# OpenDeck-r1_2_2.net
KiCad netlist of a schematic drawn in EAGLE
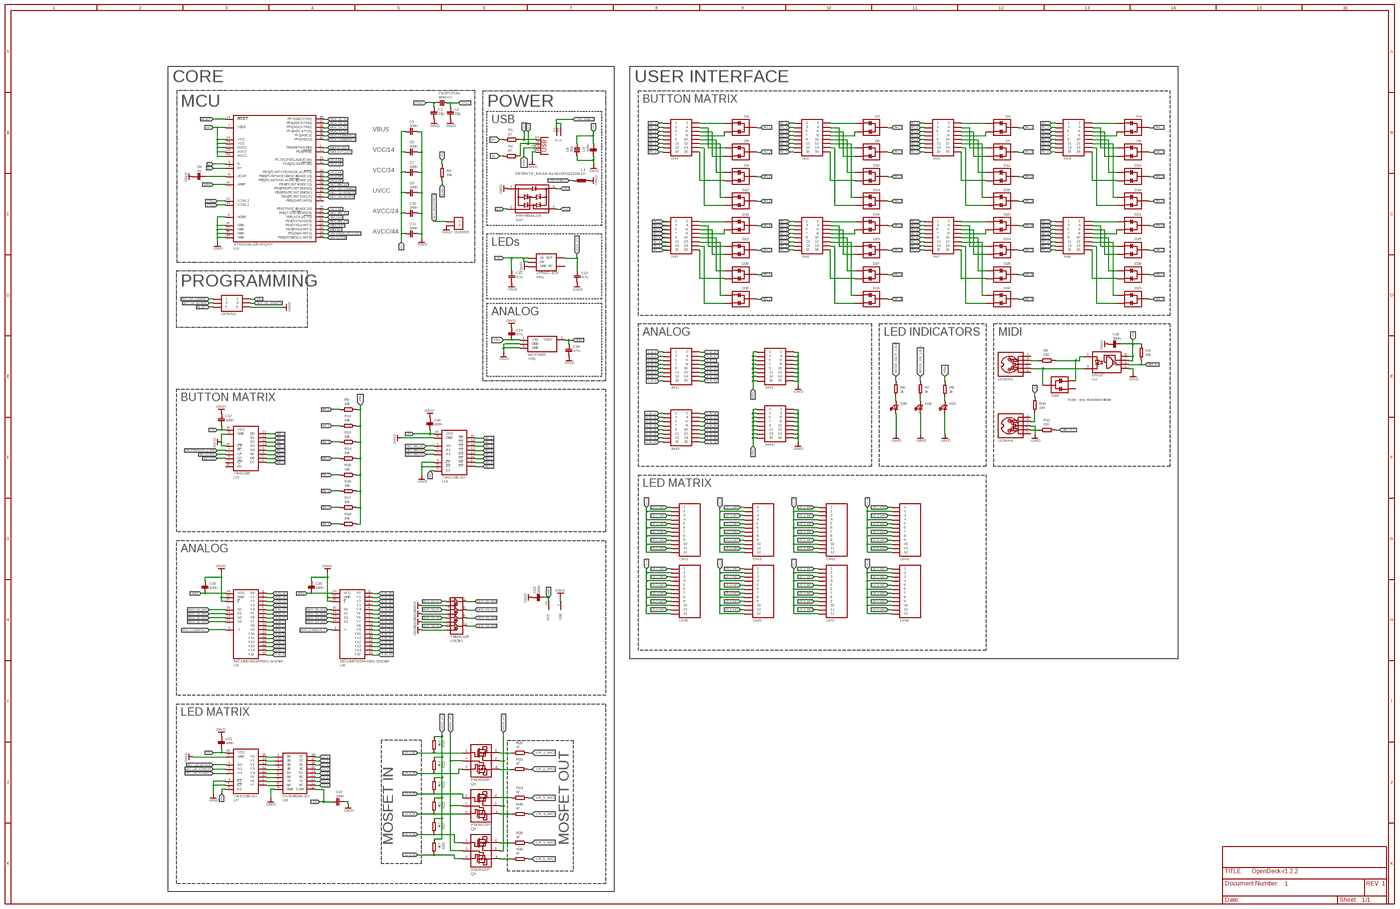
[diagram p0: schematic, sheet 1, overview]
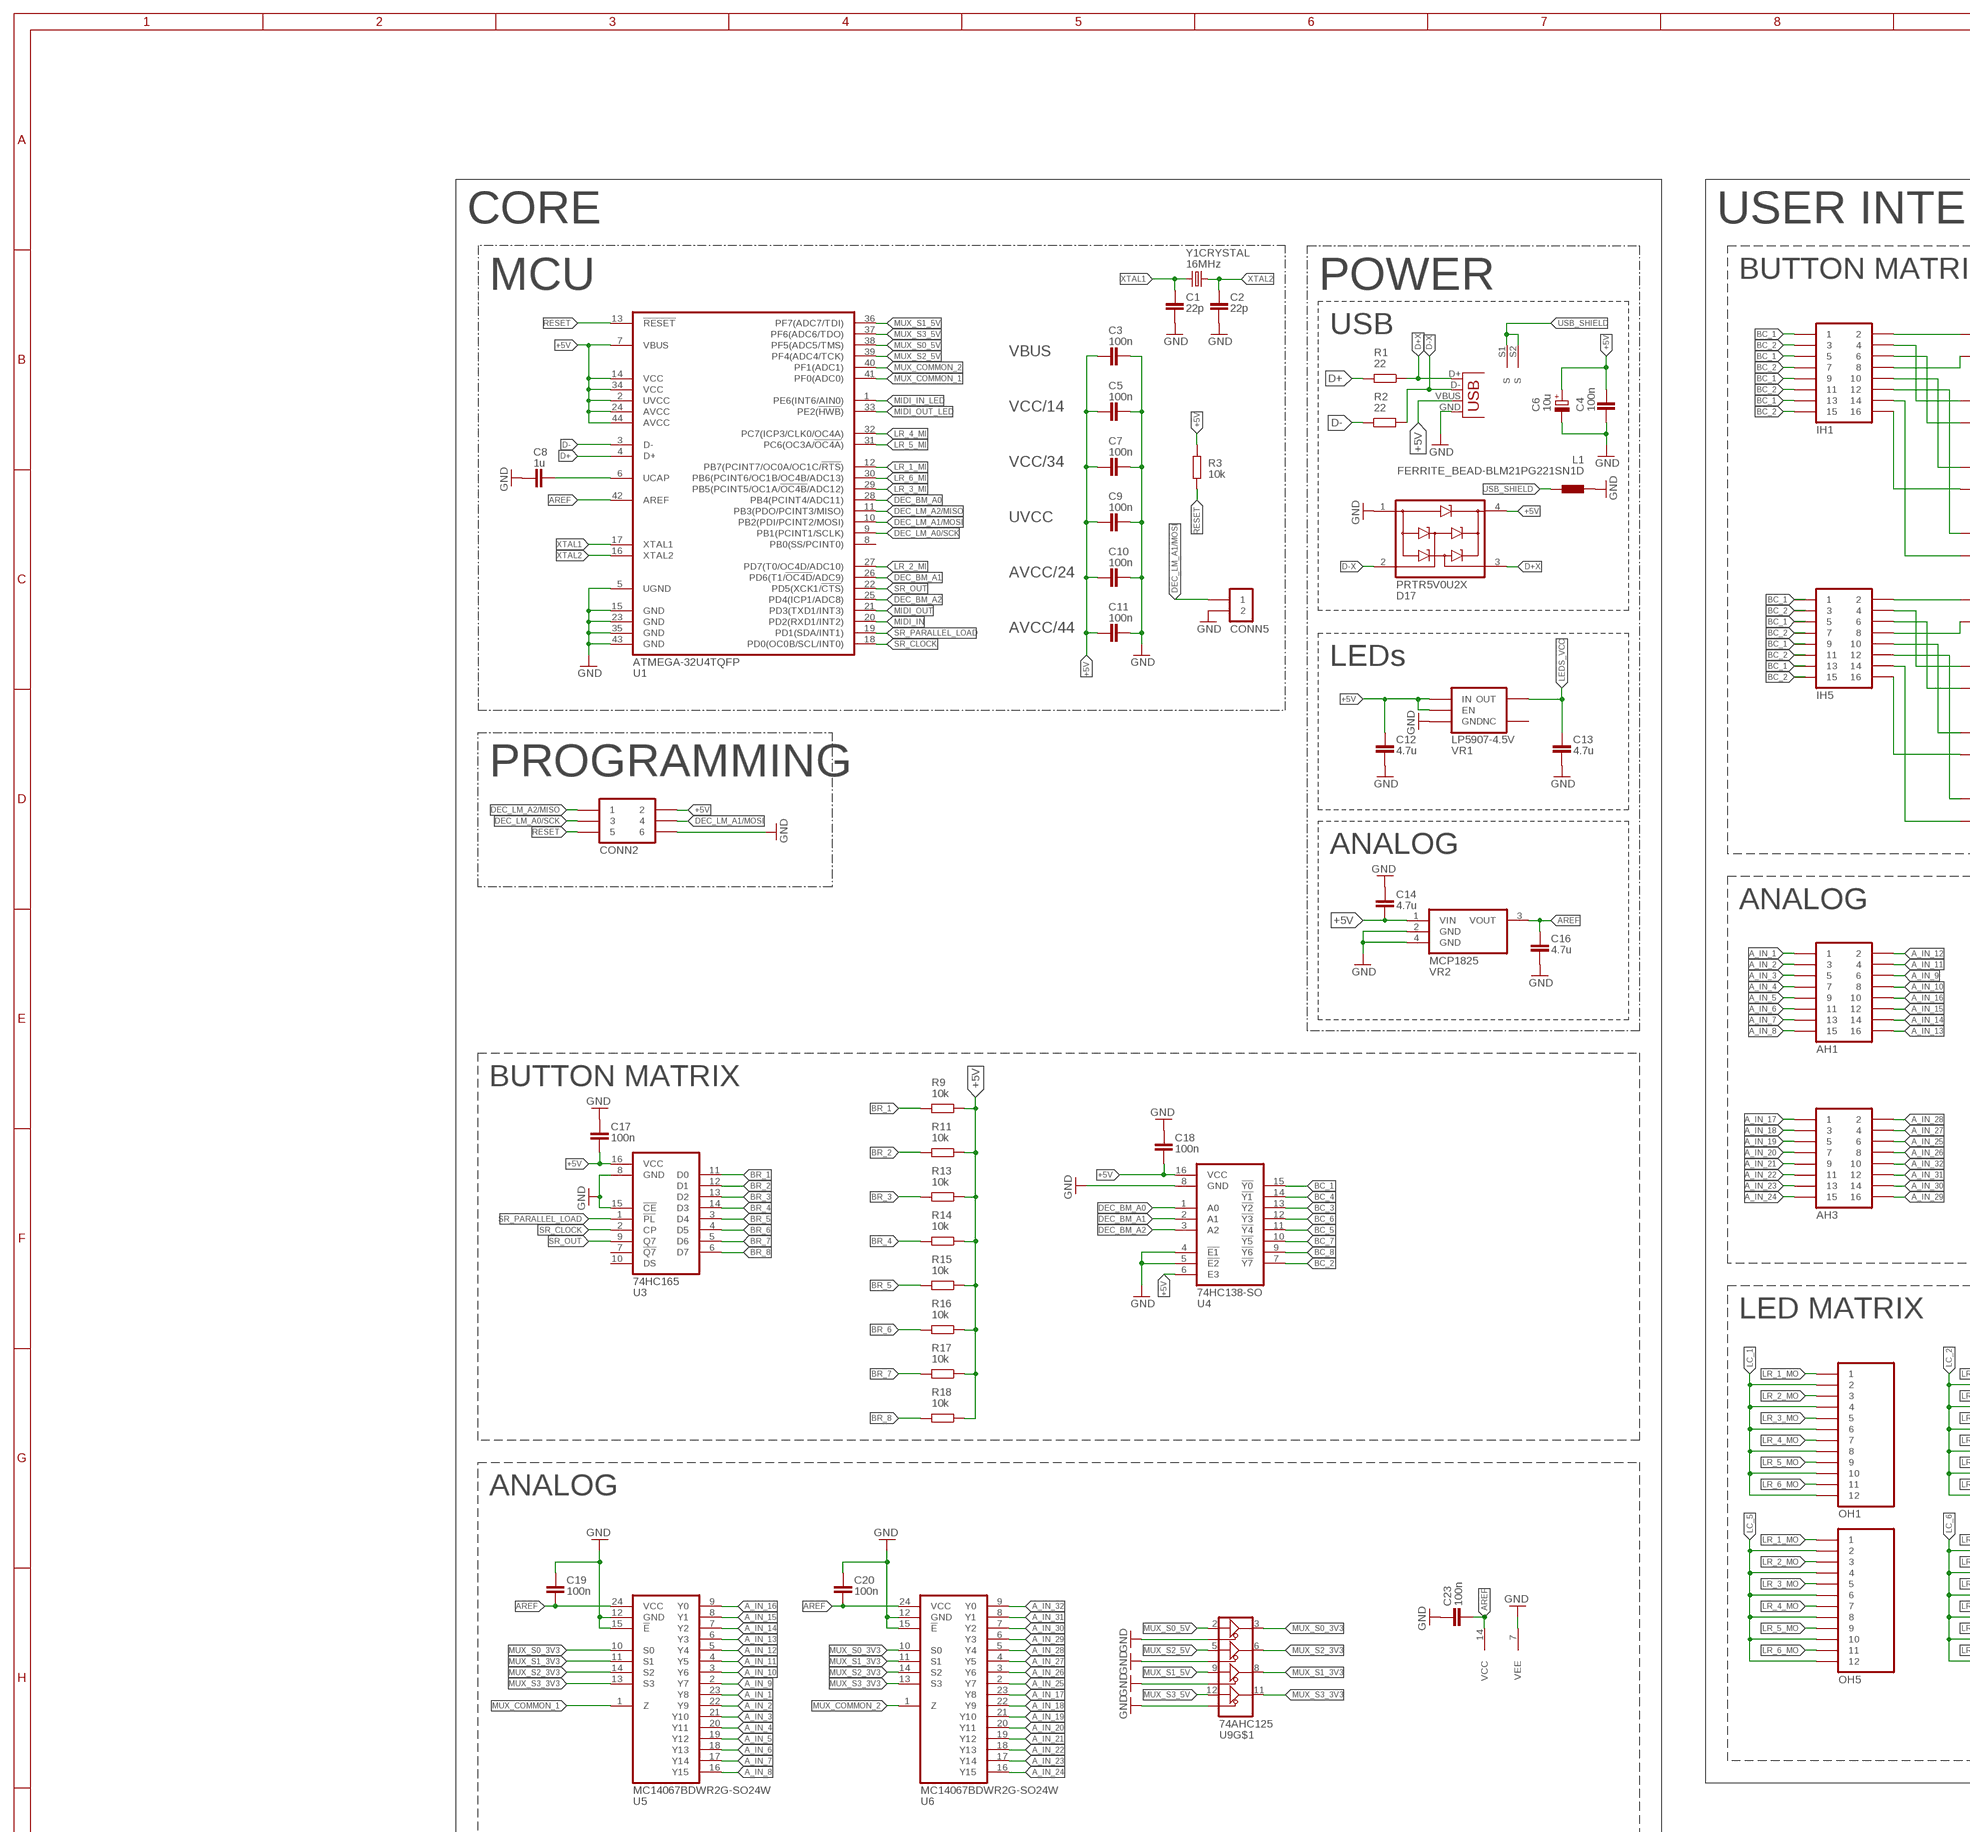
[diagram p1: schematic, sheet 1, part 1 of 4]
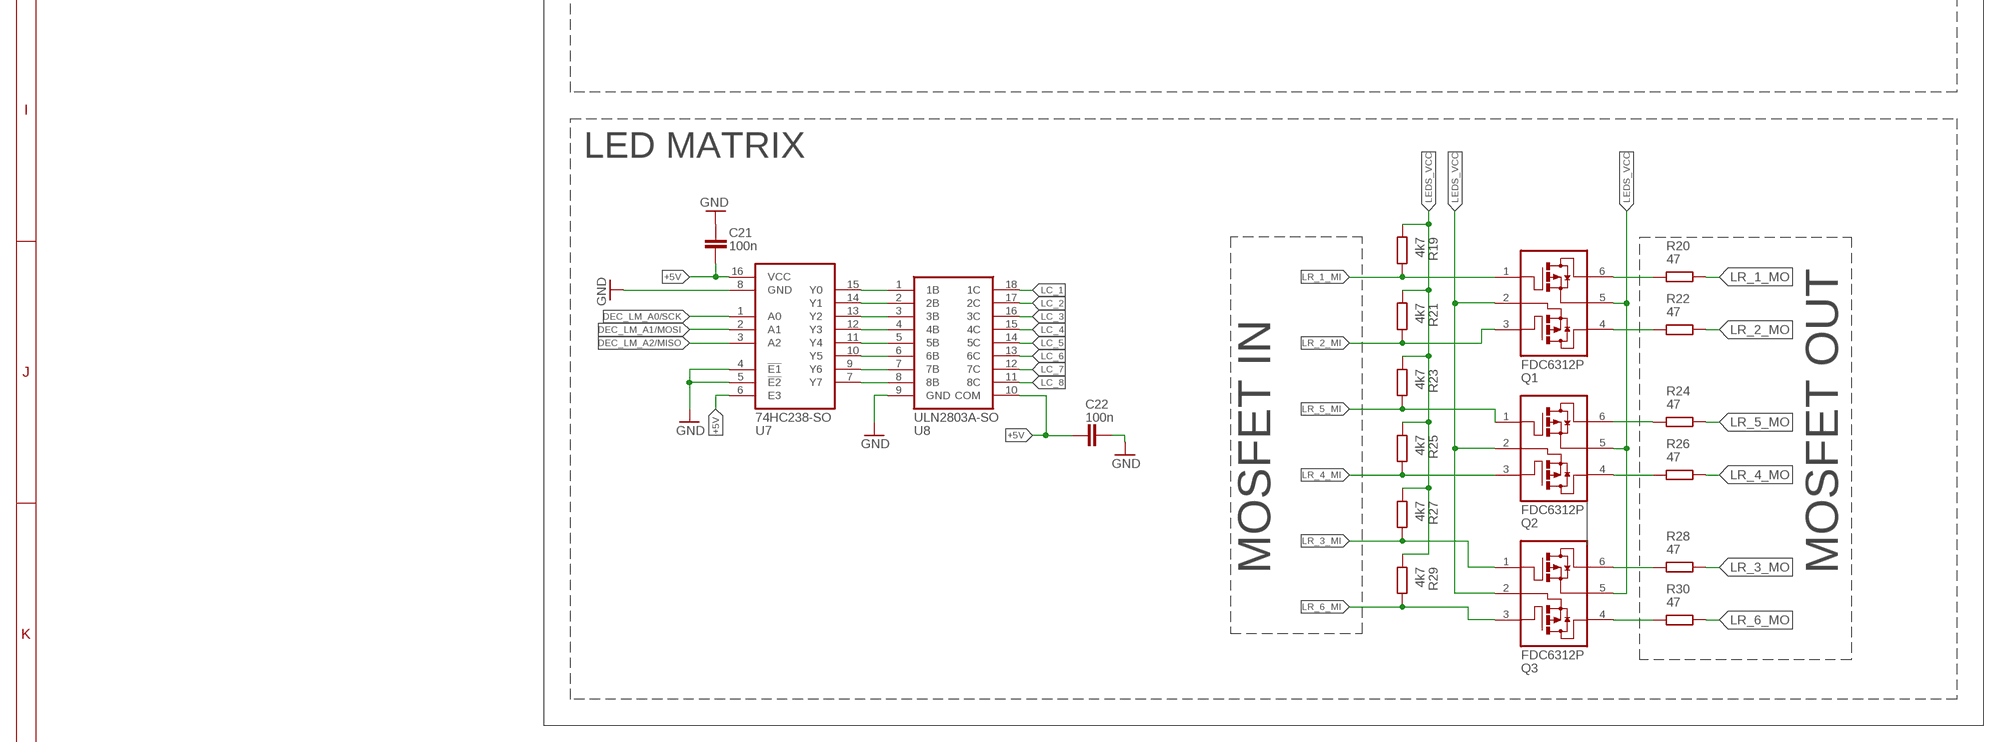
[diagram p2: schematic, sheet 1, part 2 of 4]
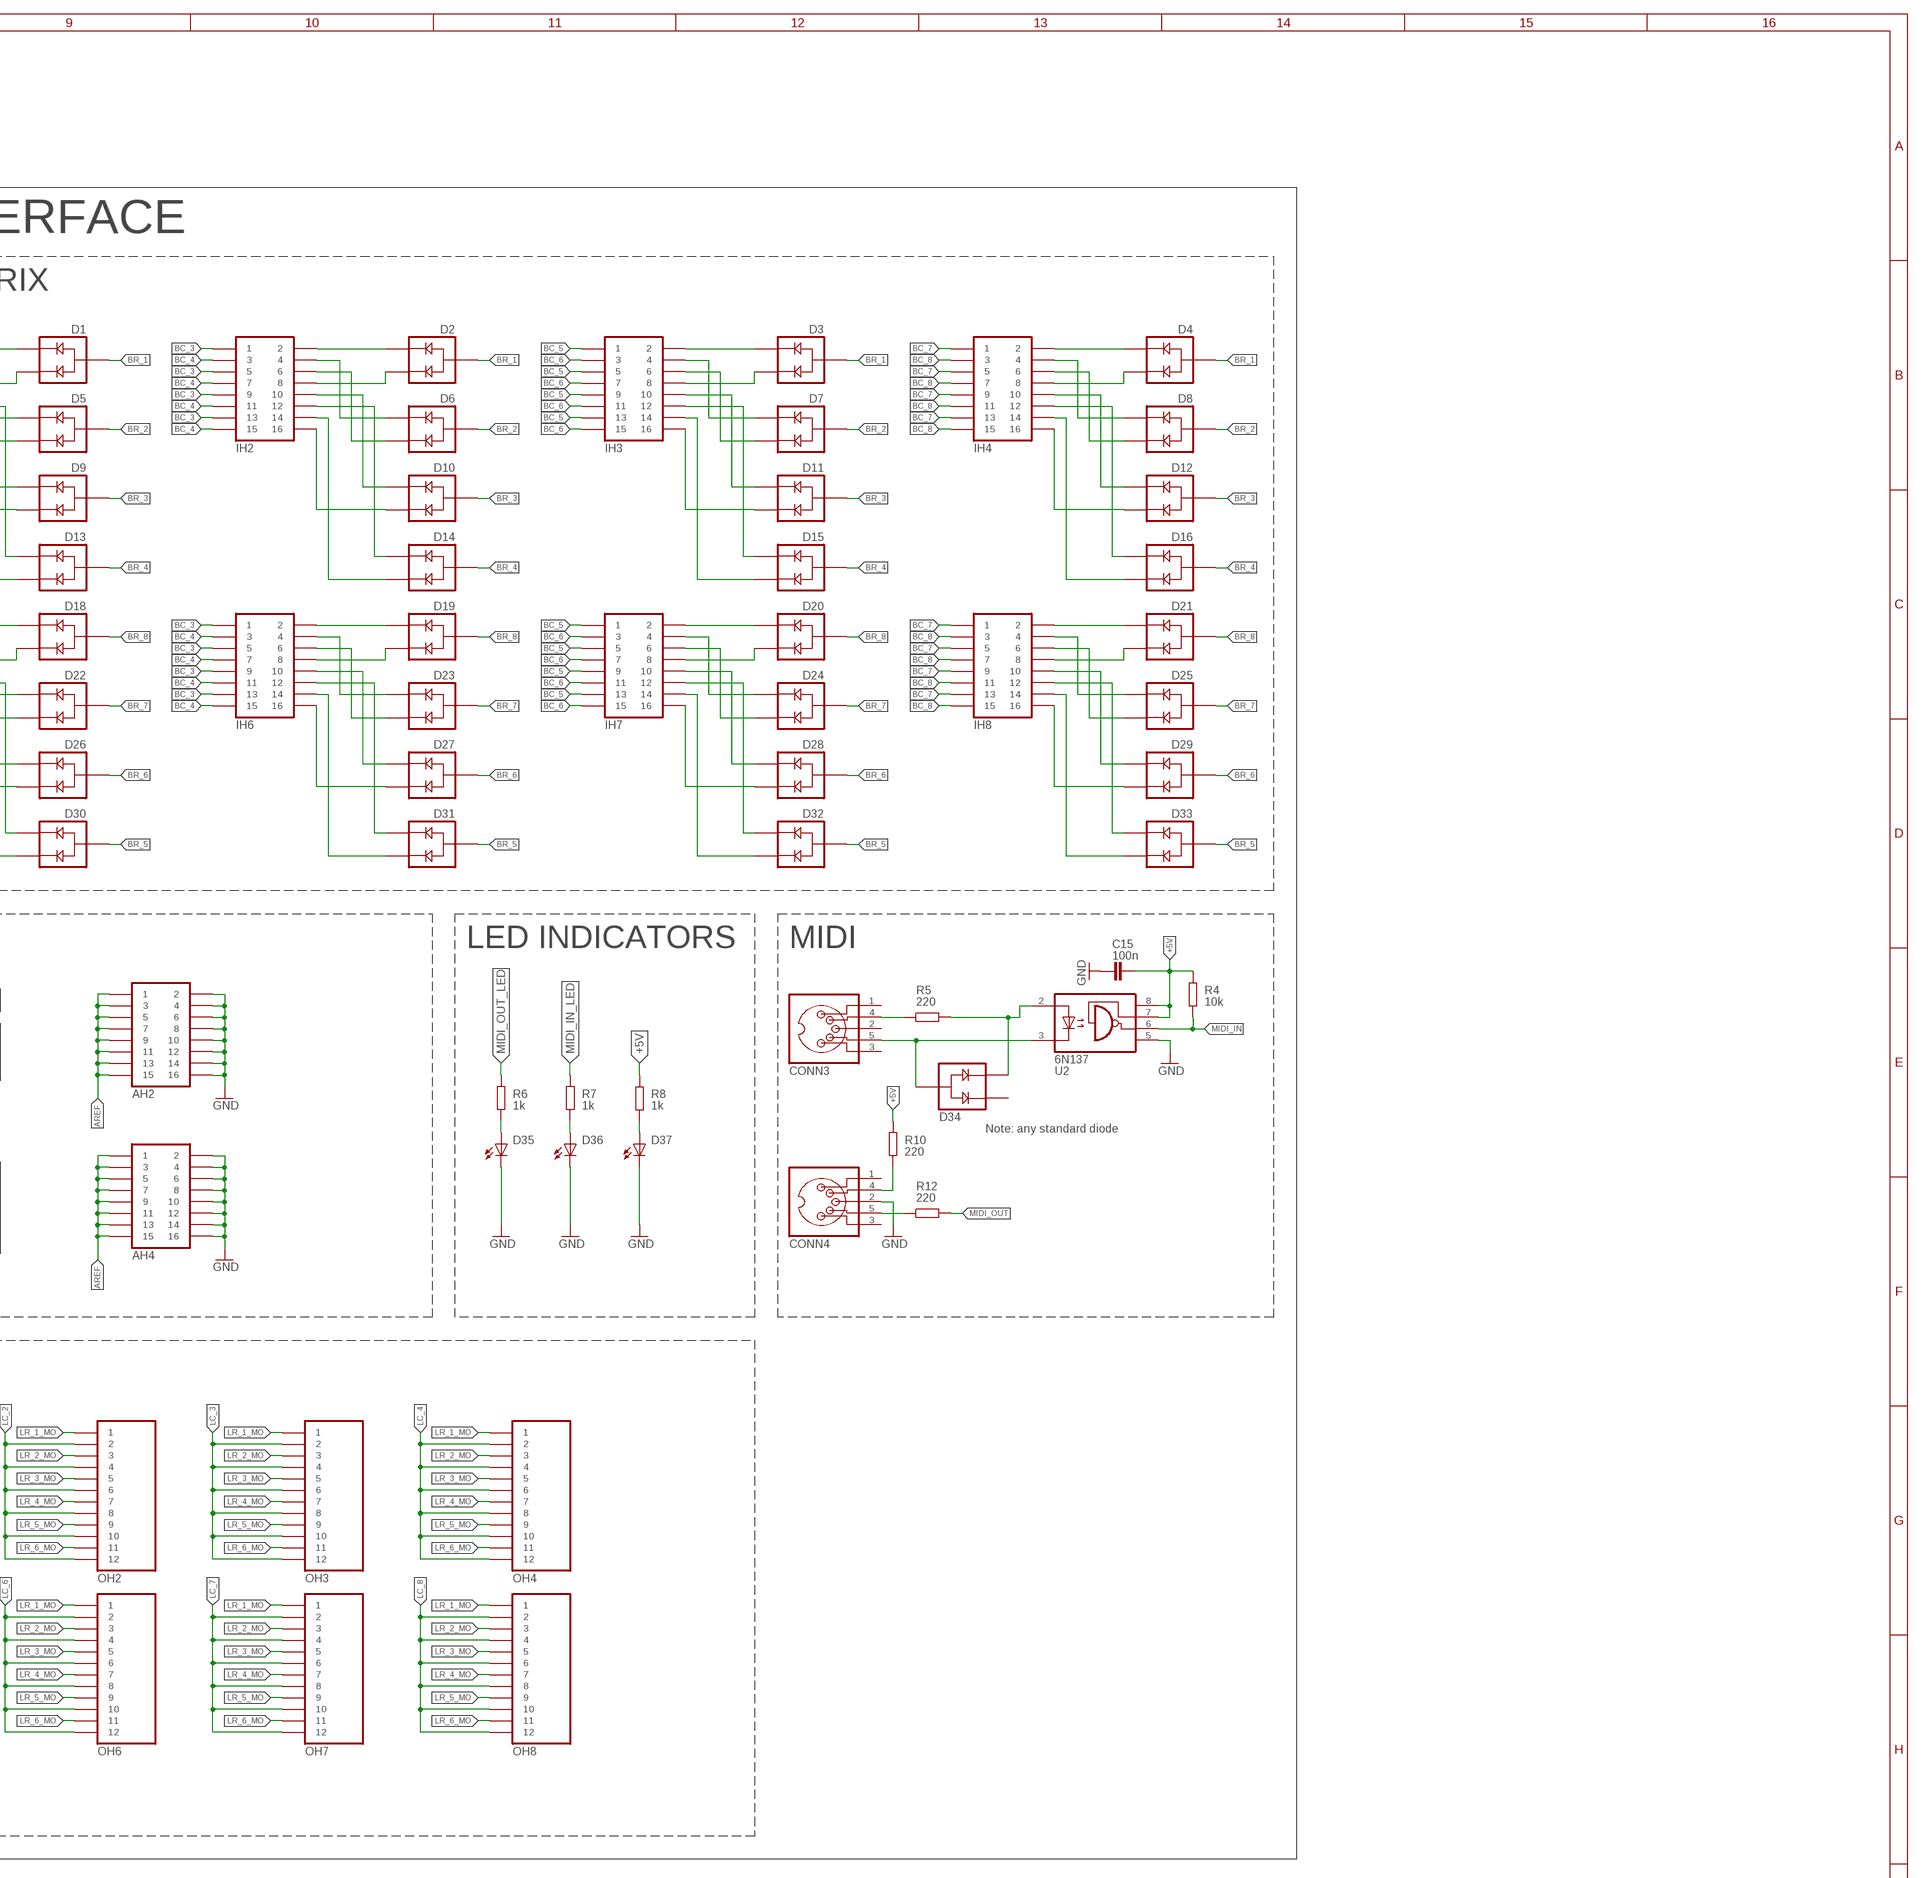
[diagram p3: schematic, sheet 1, part 3 of 4]
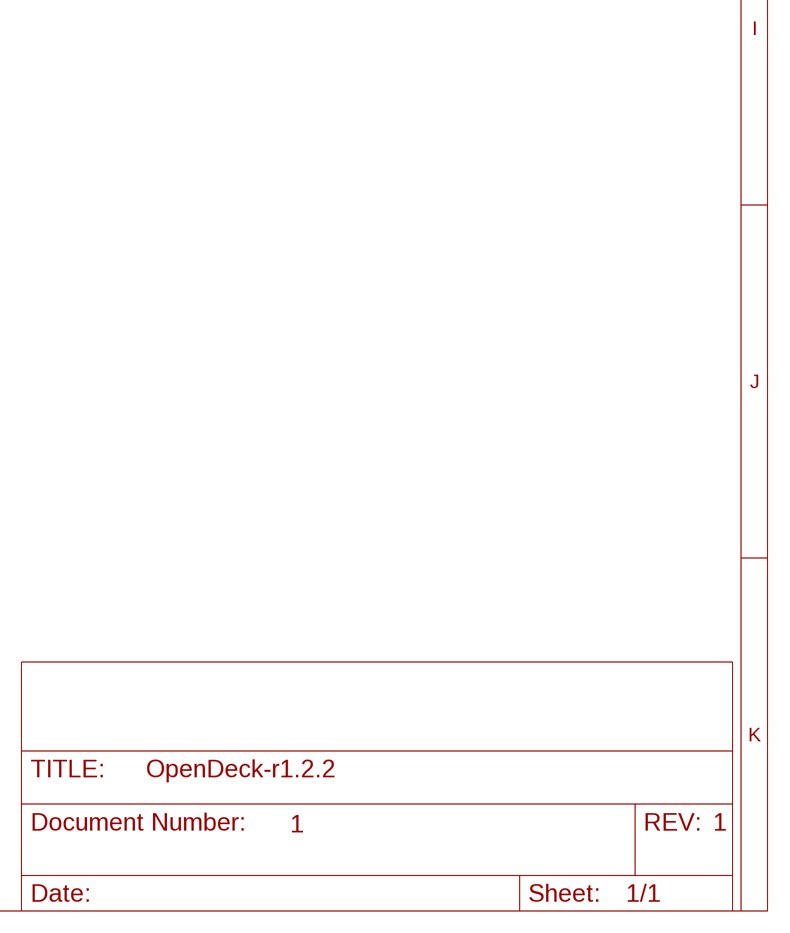
[diagram p4: schematic, sheet 1, part 4 of 4]

(export (version "E")
  (design (tool "Eeschema 10.0.6"))
  (components
    (comp (ref "AH1")
      (value "PINHD-2X08-TH-2.54MM")
      (footprint "eagle-import:2X08-2.54")
      (libsource (lib "eagle-import") (part "PINHD-2X08-TH-2.54MM"))
    )
    (comp (ref "AH2")
      (value "PINHD-2X08-TH-2.54MM")
      (footprint "eagle-import:2X08-2.54")
      (libsource (lib "eagle-import") (part "PINHD-2X08-TH-2.54MM"))
    )
    (comp (ref "AH3")
      (value "PINHD-2X08-TH-2.54MM")
      (footprint "eagle-import:2X08-2.54")
      (libsource (lib "eagle-import") (part "PINHD-2X08-TH-2.54MM"))
    )
    (comp (ref "AH4")
      (value "PINHD-2X08-TH-2.54MM")
      (footprint "eagle-import:2X08-2.54")
      (libsource (lib "eagle-import") (part "PINHD-2X08-TH-2.54MM"))
    )
    (comp (ref "C1")
      (value "22p")
      (footprint "eagle-import:C0603")
      (libsource (lib "eagle-import") (part "CAPACITOR-0603"))
    )
    (comp (ref "C2")
      (value "22p")
      (footprint "eagle-import:C0603")
      (libsource (lib "eagle-import") (part "CAPACITOR-0603"))
    )
    (comp (ref "C3")
      (value "100n")
      (footprint "eagle-import:C0603")
      (libsource (lib "eagle-import") (part "CAPACITOR-0603"))
    )
    (comp (ref "C4")
      (value "100n")
      (footprint "eagle-import:C0603")
      (libsource (lib "eagle-import") (part "CAPACITOR-0603"))
    )
    (comp (ref "C5")
      (value "100n")
      (footprint "eagle-import:C0603")
      (libsource (lib "eagle-import") (part "CAPACITOR-0603"))
    )
    (comp (ref "C6")
      (value "10u")
      (footprint "eagle-import:153CLV-0405")
      (fields (field (name "MANUFACTURER") "Multicomp") (field (name "MPN") "MCVVT016M100CA1L"))
      (libsource (lib "eagle-import") (part "ELECTROLYTIC_CAPACITOR-CLV-040516V"))
    )
    (comp (ref "C7")
      (value "100n")
      (footprint "eagle-import:C0603")
      (libsource (lib "eagle-import") (part "CAPACITOR-0603"))
    )
    (comp (ref "C8")
      (value "1u")
      (footprint "eagle-import:C0603")
      (libsource (lib "eagle-import") (part "CAPACITOR-0603"))
    )
    (comp (ref "C9")
      (value "100n")
      (footprint "eagle-import:C0603")
      (libsource (lib "eagle-import") (part "CAPACITOR-0603"))
    )
    (comp (ref "C10")
      (value "100n")
      (footprint "eagle-import:C0603")
      (libsource (lib "eagle-import") (part "CAPACITOR-0603"))
    )
    (comp (ref "C11")
      (value "100n")
      (footprint "eagle-import:C0603")
      (libsource (lib "eagle-import") (part "CAPACITOR-0603"))
    )
    (comp (ref "C12")
      (value "4.7u")
      (footprint "eagle-import:C0603")
      (libsource (lib "eagle-import") (part "CAPACITOR-0603"))
    )
    (comp (ref "C13")
      (value "4.7u")
      (footprint "eagle-import:C0603")
      (libsource (lib "eagle-import") (part "CAPACITOR-0603"))
    )
    (comp (ref "C14")
      (value "4.7u")
      (footprint "eagle-import:C0603")
      (libsource (lib "eagle-import") (part "CAPACITOR-0603"))
    )
    (comp (ref "C15")
      (value "100n")
      (footprint "eagle-import:C0603")
      (libsource (lib "eagle-import") (part "CAPACITOR-0603"))
    )
    (comp (ref "C16")
      (value "4.7u")
      (footprint "eagle-import:C0603")
      (libsource (lib "eagle-import") (part "CAPACITOR-0603"))
    )
    (comp (ref "C17")
      (value "100n")
      (footprint "eagle-import:C0603")
      (libsource (lib "eagle-import") (part "CAPACITOR-0603"))
    )
    (comp (ref "C18")
      (value "100n")
      (footprint "eagle-import:C0603")
      (libsource (lib "eagle-import") (part "CAPACITOR-0603"))
    )
    (comp (ref "C19")
      (value "100n")
      (footprint "eagle-import:C0603")
      (libsource (lib "eagle-import") (part "CAPACITOR-0603"))
    )
    (comp (ref "C20")
      (value "100n")
      (footprint "eagle-import:C0603")
      (libsource (lib "eagle-import") (part "CAPACITOR-0603"))
    )
    (comp (ref "C21")
      (value "100n")
      (footprint "eagle-import:C0603")
      (libsource (lib "eagle-import") (part "CAPACITOR-0603"))
    )
    (comp (ref "C22")
      (value "100n")
      (footprint "eagle-import:C0603")
      (libsource (lib "eagle-import") (part "CAPACITOR-0603"))
    )
    (comp (ref "C23")
      (value "100n")
      (footprint "eagle-import:C0603")
      (libsource (lib "eagle-import") (part "CAPACITOR-0603"))
    )
    (comp (ref "CONN1")
      (value "USB-B-PTH")
      (footprint "eagle-import:USB-B-PTH")
      (libsource (lib "eagle-import") (part "USB-B-PTH"))
    )
    (comp (ref "CONN2")
      (value "PINHD-2X03-TH-2.54MM-V")
      (footprint "eagle-import:2X03-2.54-V")
      (libsource (lib "eagle-import") (part "PINHD-2X03-TH-2.54MM-V"))
    )
    (comp (ref "CONN3")
      (value "MIDI_CONN-STD")
      (footprint "eagle-import:DIN5_SUPPORT")
      (libsource (lib "eagle-import") (part "MIDI_CONN-STD"))
    )
    (comp (ref "CONN4")
      (value "MIDI_CONN-STD")
      (footprint "eagle-import:DIN5_SUPPORT")
      (libsource (lib "eagle-import") (part "MIDI_CONN-STD"))
    )
    (comp (ref "CONN5")
      (value "PINHD-1X02-TH-2.54MM")
      (footprint "eagle-import:1X02-2.54-V")
      (libsource (lib "eagle-import") (part "PINHD-1X02-TH-2.54MM"))
    )
    (comp (ref "D1")
      (value "BAW56")
      (footprint "eagle-import:SOT23")
      (fields (field (name "MANUFACTURER") "Multicomp") (field (name "MPN") "BAW56-7-F"))
      (libsource (lib "eagle-import") (part "BAW56"))
    )
    (comp (ref "D2")
      (value "BAW56")
      (footprint "eagle-import:SOT23")
      (fields (field (name "MANUFACTURER") "Multicomp") (field (name "MPN") "BAW56-7-F"))
      (libsource (lib "eagle-import") (part "BAW56"))
    )
    (comp (ref "D3")
      (value "BAW56")
      (footprint "eagle-import:SOT23")
      (fields (field (name "MANUFACTURER") "Multicomp") (field (name "MPN") "BAW56-7-F"))
      (libsource (lib "eagle-import") (part "BAW56"))
    )
    (comp (ref "D4")
      (value "BAW56")
      (footprint "eagle-import:SOT23")
      (fields (field (name "MANUFACTURER") "Multicomp") (field (name "MPN") "BAW56-7-F"))
      (libsource (lib "eagle-import") (part "BAW56"))
    )
    (comp (ref "D5")
      (value "BAW56")
      (footprint "eagle-import:SOT23")
      (fields (field (name "MANUFACTURER") "Multicomp") (field (name "MPN") "BAW56-7-F"))
      (libsource (lib "eagle-import") (part "BAW56"))
    )
    (comp (ref "D6")
      (value "BAW56")
      (footprint "eagle-import:SOT23")
      (fields (field (name "MANUFACTURER") "Multicomp") (field (name "MPN") "BAW56-7-F"))
      (libsource (lib "eagle-import") (part "BAW56"))
    )
    (comp (ref "D7")
      (value "BAW56")
      (footprint "eagle-import:SOT23")
      (fields (field (name "MANUFACTURER") "Multicomp") (field (name "MPN") "BAW56-7-F"))
      (libsource (lib "eagle-import") (part "BAW56"))
    )
    (comp (ref "D8")
      (value "BAW56")
      (footprint "eagle-import:SOT23")
      (fields (field (name "MANUFACTURER") "Multicomp") (field (name "MPN") "BAW56-7-F"))
      (libsource (lib "eagle-import") (part "BAW56"))
    )
    (comp (ref "D9")
      (value "BAW56")
      (footprint "eagle-import:SOT23")
      (fields (field (name "MANUFACTURER") "Multicomp") (field (name "MPN") "BAW56-7-F"))
      (libsource (lib "eagle-import") (part "BAW56"))
    )
    (comp (ref "D10")
      (value "BAW56")
      (footprint "eagle-import:SOT23")
      (fields (field (name "MANUFACTURER") "Multicomp") (field (name "MPN") "BAW56-7-F"))
      (libsource (lib "eagle-import") (part "BAW56"))
    )
    (comp (ref "D11")
      (value "BAW56")
      (footprint "eagle-import:SOT23")
      (fields (field (name "MANUFACTURER") "Multicomp") (field (name "MPN") "BAW56-7-F"))
      (libsource (lib "eagle-import") (part "BAW56"))
    )
    (comp (ref "D12")
      (value "BAW56")
      (footprint "eagle-import:SOT23")
      (fields (field (name "MANUFACTURER") "Multicomp") (field (name "MPN") "BAW56-7-F"))
      (libsource (lib "eagle-import") (part "BAW56"))
    )
    (comp (ref "D13")
      (value "BAW56")
      (footprint "eagle-import:SOT23")
      (fields (field (name "MANUFACTURER") "Multicomp") (field (name "MPN") "BAW56-7-F"))
      (libsource (lib "eagle-import") (part "BAW56"))
    )
    (comp (ref "D14")
      (value "BAW56")
      (footprint "eagle-import:SOT23")
      (fields (field (name "MANUFACTURER") "Multicomp") (field (name "MPN") "BAW56-7-F"))
      (libsource (lib "eagle-import") (part "BAW56"))
    )
    (comp (ref "D15")
      (value "BAW56")
      (footprint "eagle-import:SOT23")
      (fields (field (name "MANUFACTURER") "Multicomp") (field (name "MPN") "BAW56-7-F"))
      (libsource (lib "eagle-import") (part "BAW56"))
    )
    (comp (ref "D16")
      (value "BAW56")
      (footprint "eagle-import:SOT23")
      (fields (field (name "MANUFACTURER") "Multicomp") (field (name "MPN") "BAW56-7-F"))
      (libsource (lib "eagle-import") (part "BAW56"))
    )
    (comp (ref "D17")
      (value "PRTR5V0U2X")
      (footprint "eagle-import:SOT143")
      (fields (field (name "MANUFACTURER") "Nexperia"))
      (libsource (lib "eagle-import") (part "PRTR5V0U2X"))
    )
    (comp (ref "D18")
      (value "BAW56")
      (footprint "eagle-import:SOT23")
      (fields (field (name "MANUFACTURER") "Multicomp") (field (name "MPN") "BAW56-7-F"))
      (libsource (lib "eagle-import") (part "BAW56"))
    )
    (comp (ref "D19")
      (value "BAW56")
      (footprint "eagle-import:SOT23")
      (fields (field (name "MANUFACTURER") "Multicomp") (field (name "MPN") "BAW56-7-F"))
      (libsource (lib "eagle-import") (part "BAW56"))
    )
    (comp (ref "D20")
      (value "BAW56")
      (footprint "eagle-import:SOT23")
      (fields (field (name "MANUFACTURER") "Multicomp") (field (name "MPN") "BAW56-7-F"))
      (libsource (lib "eagle-import") (part "BAW56"))
    )
    (comp (ref "D21")
      (value "BAW56")
      (footprint "eagle-import:SOT23")
      (fields (field (name "MANUFACTURER") "Multicomp") (field (name "MPN") "BAW56-7-F"))
      (libsource (lib "eagle-import") (part "BAW56"))
    )
    (comp (ref "D22")
      (value "BAW56")
      (footprint "eagle-import:SOT23")
      (fields (field (name "MANUFACTURER") "Multicomp") (field (name "MPN") "BAW56-7-F"))
      (libsource (lib "eagle-import") (part "BAW56"))
    )
    (comp (ref "D23")
      (value "BAW56")
      (footprint "eagle-import:SOT23")
      (fields (field (name "MANUFACTURER") "Multicomp") (field (name "MPN") "BAW56-7-F"))
      (libsource (lib "eagle-import") (part "BAW56"))
    )
    (comp (ref "D24")
      (value "BAW56")
      (footprint "eagle-import:SOT23")
      (fields (field (name "MANUFACTURER") "Multicomp") (field (name "MPN") "BAW56-7-F"))
      (libsource (lib "eagle-import") (part "BAW56"))
    )
    (comp (ref "D25")
      (value "BAW56")
      (footprint "eagle-import:SOT23")
      (fields (field (name "MANUFACTURER") "Multicomp") (field (name "MPN") "BAW56-7-F"))
      (libsource (lib "eagle-import") (part "BAW56"))
    )
    (comp (ref "D26")
      (value "BAW56")
      (footprint "eagle-import:SOT23")
      (fields (field (name "MANUFACTURER") "Multicomp") (field (name "MPN") "BAW56-7-F"))
      (libsource (lib "eagle-import") (part "BAW56"))
    )
    (comp (ref "D27")
      (value "BAW56")
      (footprint "eagle-import:SOT23")
      (fields (field (name "MANUFACTURER") "Multicomp") (field (name "MPN") "BAW56-7-F"))
      (libsource (lib "eagle-import") (part "BAW56"))
    )
    (comp (ref "D28")
      (value "BAW56")
      (footprint "eagle-import:SOT23")
      (fields (field (name "MANUFACTURER") "Multicomp") (field (name "MPN") "BAW56-7-F"))
      (libsource (lib "eagle-import") (part "BAW56"))
    )
    (comp (ref "D29")
      (value "BAW56")
      (footprint "eagle-import:SOT23")
      (fields (field (name "MANUFACTURER") "Multicomp") (field (name "MPN") "BAW56-7-F"))
      (libsource (lib "eagle-import") (part "BAW56"))
    )
    (comp (ref "D30")
      (value "BAW56")
      (footprint "eagle-import:SOT23")
      (fields (field (name "MANUFACTURER") "Multicomp") (field (name "MPN") "BAW56-7-F"))
      (libsource (lib "eagle-import") (part "BAW56"))
    )
    (comp (ref "D31")
      (value "BAW56")
      (footprint "eagle-import:SOT23")
      (fields (field (name "MANUFACTURER") "Multicomp") (field (name "MPN") "BAW56-7-F"))
      (libsource (lib "eagle-import") (part "BAW56"))
    )
    (comp (ref "D32")
      (value "BAW56")
      (footprint "eagle-import:SOT23")
      (fields (field (name "MANUFACTURER") "Multicomp") (field (name "MPN") "BAW56-7-F"))
      (libsource (lib "eagle-import") (part "BAW56"))
    )
    (comp (ref "D33")
      (value "BAW56")
      (footprint "eagle-import:SOT23")
      (fields (field (name "MANUFACTURER") "Multicomp") (field (name "MPN") "BAW56-7-F"))
      (libsource (lib "eagle-import") (part "BAW56"))
    )
    (comp (ref "D34")
      (value "BAW56")
      (footprint "eagle-import:SOT23")
      (fields (field (name "MANUFACTURER") "Multicomp") (field (name "MPN") "BAW56-7-F"))
      (libsource (lib "eagle-import") (part "BAW56"))
    )
    (comp (ref "D35")
      (value "Red")
      (footprint "eagle-import:0805_LED")
      (libsource (lib "eagle-import") (part "LED-0805"))
    )
    (comp (ref "D36")
      (value "Yellow")
      (footprint "eagle-import:0805_LED")
      (libsource (lib "eagle-import") (part "LED-0805"))
    )
    (comp (ref "D37")
      (value "Green")
      (footprint "eagle-import:0805_LED")
      (libsource (lib "eagle-import") (part "LED-0805"))
    )
    (comp (ref "IH1")
      (value "PINHD-2X08-TH-2.54MM")
      (footprint "eagle-import:2X08-2.54")
      (libsource (lib "eagle-import") (part "PINHD-2X08-TH-2.54MM"))
    )
    (comp (ref "IH2")
      (value "PINHD-2X08-TH-2.54MM")
      (footprint "eagle-import:2X08-2.54")
      (libsource (lib "eagle-import") (part "PINHD-2X08-TH-2.54MM"))
    )
    (comp (ref "IH3")
      (value "PINHD-2X08-TH-2.54MM")
      (footprint "eagle-import:2X08-2.54")
      (libsource (lib "eagle-import") (part "PINHD-2X08-TH-2.54MM"))
    )
    (comp (ref "IH4")
      (value "PINHD-2X08-TH-2.54MM")
      (footprint "eagle-import:2X08-2.54")
      (libsource (lib "eagle-import") (part "PINHD-2X08-TH-2.54MM"))
    )
    (comp (ref "IH5")
      (value "PINHD-2X08-TH-2.54MM")
      (footprint "eagle-import:2X08-2.54")
      (libsource (lib "eagle-import") (part "PINHD-2X08-TH-2.54MM"))
    )
    (comp (ref "IH6")
      (value "PINHD-2X08-TH-2.54MM")
      (footprint "eagle-import:2X08-2.54")
      (libsource (lib "eagle-import") (part "PINHD-2X08-TH-2.54MM"))
    )
    (comp (ref "IH7")
      (value "PINHD-2X08-TH-2.54MM")
      (footprint "eagle-import:2X08-2.54")
      (libsource (lib "eagle-import") (part "PINHD-2X08-TH-2.54MM"))
    )
    (comp (ref "IH8")
      (value "PINHD-2X08-TH-2.54MM")
      (footprint "eagle-import:2X08-2.54")
      (libsource (lib "eagle-import") (part "PINHD-2X08-TH-2.54MM"))
    )
    (comp (ref "L1")
      (value "FERRITE_BEAD-BLM21PG221SN1D")
      (footprint "eagle-import:L0805")
      (fields (field (name "MANUFACTURER") "Murata") (field (name "MPN") "BLM21PG221SN1D"))
      (libsource (lib "eagle-import") (part "FERRITE_BEAD-BLM21PG221SN1D"))
    )
    (comp (ref "OH1")
      (value "PINHD-2X06-TH-2.54MM")
      (footprint "eagle-import:2X06-2.54-V")
      (libsource (lib "eagle-import") (part "PINHD-2X06-TH-2.54MM"))
    )
    (comp (ref "OH2")
      (value "PINHD-2X06-TH-2.54MM")
      (footprint "eagle-import:2X06-2.54-V")
      (libsource (lib "eagle-import") (part "PINHD-2X06-TH-2.54MM"))
    )
    (comp (ref "OH3")
      (value "PINHD-2X06-TH-2.54MM")
      (footprint "eagle-import:2X06-2.54-V")
      (libsource (lib "eagle-import") (part "PINHD-2X06-TH-2.54MM"))
    )
    (comp (ref "OH4")
      (value "PINHD-2X06-TH-2.54MM")
      (footprint "eagle-import:2X06-2.54-V")
      (libsource (lib "eagle-import") (part "PINHD-2X06-TH-2.54MM"))
    )
    (comp (ref "OH5")
      (value "PINHD-2X06-TH-2.54MM")
      (footprint "eagle-import:2X06-2.54-V")
      (libsource (lib "eagle-import") (part "PINHD-2X06-TH-2.54MM"))
    )
    (comp (ref "OH6")
      (value "PINHD-2X06-TH-2.54MM")
      (footprint "eagle-import:2X06-2.54-V")
      (libsource (lib "eagle-import") (part "PINHD-2X06-TH-2.54MM"))
    )
    (comp (ref "OH7")
      (value "PINHD-2X06-TH-2.54MM")
      (footprint "eagle-import:2X06-2.54-V")
      (libsource (lib "eagle-import") (part "PINHD-2X06-TH-2.54MM"))
    )
    (comp (ref "OH8")
      (value "PINHD-2X06-TH-2.54MM")
      (footprint "eagle-import:2X06-2.54-V")
      (libsource (lib "eagle-import") (part "PINHD-2X06-TH-2.54MM"))
    )
    (comp (ref "Q1")
      (value "FDC6312P")
      (footprint "eagle-import:SSOT6")
      (fields (field (name "MANUFACTURER") "ON Semiconductor"))
      (libsource (lib "eagle-import") (part "FDC6312P"))
    )
    (comp (ref "Q2")
      (value "FDC6312P")
      (footprint "eagle-import:SSOT6")
      (fields (field (name "MANUFACTURER") "ON Semiconductor"))
      (libsource (lib "eagle-import") (part "FDC6312P"))
    )
    (comp (ref "Q3")
      (value "FDC6312P")
      (footprint "eagle-import:SSOT6")
      (fields (field (name "MANUFACTURER") "ON Semiconductor"))
      (libsource (lib "eagle-import") (part "FDC6312P"))
    )
    (comp (ref "R1")
      (value "22")
      (footprint "eagle-import:R0603")
      (libsource (lib "eagle-import") (part "RESISTOR-0603"))
    )
    (comp (ref "R2")
      (value "22")
      (footprint "eagle-import:R0603")
      (libsource (lib "eagle-import") (part "RESISTOR-0603"))
    )
    (comp (ref "R3")
      (value "10k")
      (footprint "eagle-import:R0603")
      (libsource (lib "eagle-import") (part "RESISTOR-0603"))
    )
    (comp (ref "R4")
      (value "10k")
      (footprint "eagle-import:R0603")
      (libsource (lib "eagle-import") (part "RESISTOR-0603"))
    )
    (comp (ref "R5")
      (value "220")
      (footprint "eagle-import:R0603")
      (libsource (lib "eagle-import") (part "RESISTOR-0603"))
    )
    (comp (ref "R6")
      (value "1k")
      (footprint "eagle-import:R0603")
      (libsource (lib "eagle-import") (part "RESISTOR-0603"))
    )
    (comp (ref "R7")
      (value "1k")
      (footprint "eagle-import:R0603")
      (libsource (lib "eagle-import") (part "RESISTOR-0603"))
    )
    (comp (ref "R8")
      (value "1k")
      (footprint "eagle-import:R0603")
      (libsource (lib "eagle-import") (part "RESISTOR-0603"))
    )
    (comp (ref "R9")
      (value "10k")
      (footprint "eagle-import:R0603")
      (libsource (lib "eagle-import") (part "RESISTOR-0603"))
    )
    (comp (ref "R10")
      (value "220")
      (footprint "eagle-import:R0603")
      (libsource (lib "eagle-import") (part "RESISTOR-0603"))
    )
    (comp (ref "R11")
      (value "10k")
      (footprint "eagle-import:R0603")
      (libsource (lib "eagle-import") (part "RESISTOR-0603"))
    )
    (comp (ref "R12")
      (value "220")
      (footprint "eagle-import:R0603")
      (libsource (lib "eagle-import") (part "RESISTOR-0603"))
    )
    (comp (ref "R13")
      (value "10k")
      (footprint "eagle-import:R0603")
      (libsource (lib "eagle-import") (part "RESISTOR-0603"))
    )
    (comp (ref "R14")
      (value "10k")
      (footprint "eagle-import:R0603")
      (libsource (lib "eagle-import") (part "RESISTOR-0603"))
    )
    (comp (ref "R15")
      (value "10k")
      (footprint "eagle-import:R0603")
      (libsource (lib "eagle-import") (part "RESISTOR-0603"))
    )
    (comp (ref "R16")
      (value "10k")
      (footprint "eagle-import:R0603")
      (libsource (lib "eagle-import") (part "RESISTOR-0603"))
    )
    (comp (ref "R17")
      (value "10k")
      (footprint "eagle-import:R0603")
      (libsource (lib "eagle-import") (part "RESISTOR-0603"))
    )
    (comp (ref "R18")
      (value "10k")
      (footprint "eagle-import:R0603")
      (libsource (lib "eagle-import") (part "RESISTOR-0603"))
    )
    (comp (ref "R19")
      (value "4k7")
      (footprint "eagle-import:R0603")
      (libsource (lib "eagle-import") (part "RESISTOR-0603"))
    )
    (comp (ref "R20")
      (value "47")
      (footprint "eagle-import:R0603")
      (libsource (lib "eagle-import") (part "RESISTOR-0603"))
    )
    (comp (ref "R21")
      (value "4k7")
      (footprint "eagle-import:R0603")
      (libsource (lib "eagle-import") (part "RESISTOR-0603"))
    )
    (comp (ref "R22")
      (value "47")
      (footprint "eagle-import:R0603")
      (libsource (lib "eagle-import") (part "RESISTOR-0603"))
    )
    (comp (ref "R23")
      (value "4k7")
      (footprint "eagle-import:R0603")
      (libsource (lib "eagle-import") (part "RESISTOR-0603"))
    )
    (comp (ref "R24")
      (value "47")
      (footprint "eagle-import:R0603")
      (libsource (lib "eagle-import") (part "RESISTOR-0603"))
    )
    (comp (ref "R25")
      (value "4k7")
      (footprint "eagle-import:R0603")
      (libsource (lib "eagle-import") (part "RESISTOR-0603"))
    )
    (comp (ref "R26")
      (value "47")
      (footprint "eagle-import:R0603")
      (libsource (lib "eagle-import") (part "RESISTOR-0603"))
    )
    (comp (ref "R27")
      (value "4k7")
      (footprint "eagle-import:R0603")
      (libsource (lib "eagle-import") (part "RESISTOR-0603"))
    )
    (comp (ref "R28")
      (value "47")
      (footprint "eagle-import:R0603")
      (libsource (lib "eagle-import") (part "RESISTOR-0603"))
    )
    (comp (ref "R29")
      (value "4k7")
      (footprint "eagle-import:R0603")
      (libsource (lib "eagle-import") (part "RESISTOR-0603"))
    )
    (comp (ref "R30")
      (value "47")
      (footprint "eagle-import:R0603")
      (libsource (lib "eagle-import") (part "RESISTOR-0603"))
    )
    (comp (ref "U1")
      (value "ATMEGA-32U4TQFP")
      (footprint "eagle-import:TQFP-44")
      (fields (field (name "MPN") "ATMEGA32U4-AUR"))
      (libsource (lib "eagle-import") (part "ATMEGA-32U4TQFP"))
    )
    (comp (ref "U2")
      (value "6N137")
      (footprint "eagle-import:DIL08")
      (fields (field (name "MANUFACTURER") "Vishay"))
      (libsource (lib "eagle-import") (part "6N137"))
    )
    (comp (ref "U3")
      (value "74HC165")
      (footprint "eagle-import:SO16")
      (fields (field (name "MANUFACTURER") "Nexperia") (field (name "MPN") "74HC165D"))
      (libsource (lib "eagle-import") (part "74165HC"))
    )
    (comp (ref "U4")
      (value "74HC138-SO")
      (footprint "eagle-import:SO16")
      (fields (field (name "MANUFACTURER") "Nexperia") (field (name "MPN") "74HC138D"))
      (libsource (lib "eagle-import") (part "74138-SOHC"))
    )
    (comp (ref "U5")
      (value "MC14067BDWR2G-SO24W")
      (footprint "eagle-import:SO24-W")
      (fields (field (name "MANUFACTURER") "ON Semiconductor") (field (name "MPN") "MC14067BDWR2G"))
      (libsource (lib "eagle-import") (part "MC14067BDWR2G-SO24W"))
    )
    (comp (ref "U6")
      (value "MC14067BDWR2G-SO24W")
      (footprint "eagle-import:SO24-W")
      (fields (field (name "MANUFACTURER") "ON Semiconductor") (field (name "MPN") "MC14067BDWR2G"))
      (libsource (lib "eagle-import") (part "MC14067BDWR2G-SO24W"))
    )
    (comp (ref "U7")
      (value "74HC238-SO")
      (footprint "eagle-import:SO16")
      (fields (field (name "MANUFACTURER") "Nexperia") (field (name "MPN") "74HC238D"))
      (libsource (lib "eagle-import") (part "74238-SOHC"))
    )
    (comp (ref "U8")
      (value "ULN2803A-SO")
      (footprint "eagle-import:SO18")
      (fields (field (name "MANUFACTURER") "Texas Instruments") (field (name "MPN") "ULN2803ADWR"))
      (libsource (lib "eagle-import") (part "ULN2803A-SO"))
    )
    (comp (ref "U9")
      (value "74AHC125")
      (footprint "eagle-import:SOIC14")
      (fields (field (name "MANUFACTURER") "Texas Instruments") (field (name "MPN") "SN74AHC125DR"))
      (libsource (lib "eagle-import") (part "74AHC125"))
    )
    (comp (ref "VR1")
      (value "LP5907-4.5V")
      (footprint "eagle-import:SOT23-5")
      (fields (field (name "MANUFACTURER") "Texas Instruments") (field (name "MPN") "LP5907MFX-4.5/NOPB"))
      (libsource (lib "eagle-import") (part "LP5907-4.5V"))
    )
    (comp (ref "VR2")
      (value "MCP1825")
      (footprint "eagle-import:SOT223")
      (fields (field (name "MANUFACTURER") "Microchip") (field (name "MPN") "MCP1825S-3302E/DB"))
      (libsource (lib "eagle-import") (part "MCP1825"))
    )
    (comp (ref "Y1")
      (value "16MHz")
      (footprint "eagle-import:CRYSTAL-SMD-3.2X2.5")
      (fields (field (name "MANUFACTURER") "TXC") (field (name "MPN") "887-1424-1-ND"))
      (libsource (lib "eagle-import") (part "CRYSTAL-4P-SMD-3.2X2.5"))
    )
  )
  (nets
    (net (code "1") (name "+5V") (class "Default")
      (node (ref "C10") (pin "1") (pinfunction "1_1") (pintype "passive"))
      (node (ref "C11") (pin "1") (pinfunction "1_1") (pintype "passive"))
      (node (ref "C12") (pin "1") (pinfunction "1_1") (pintype "passive"))
      (node (ref "C14") (pin "1") (pinfunction "1_1") (pintype "passive"))
      (node (ref "C15") (pin "2") (pinfunction "2_2") (pintype "passive"))
      (node (ref "C17") (pin "2") (pinfunction "2_2") (pintype "passive"))
      (node (ref "C18") (pin "2") (pinfunction "2_2") (pintype "passive"))
      (node (ref "C21") (pin "1") (pinfunction "1_1") (pintype "passive"))
      (node (ref "C22") (pin "1") (pinfunction "1_1") (pintype "passive"))
      (node (ref "C3") (pin "1") (pinfunction "1_1") (pintype "passive"))
      (node (ref "C4") (pin "2") (pinfunction "2_2") (pintype "passive"))
      (node (ref "C5") (pin "1") (pinfunction "1_1") (pintype "passive"))
      (node (ref "C6") (pin "+") (pinfunction "+_+") (pintype "passive"))
      (node (ref "C7") (pin "1") (pinfunction "1_1") (pintype "passive"))
      (node (ref "C9") (pin "1") (pinfunction "1_1") (pintype "passive"))
      (node (ref "CONN1") (pin "VBUS") (pinfunction "VBUS_VBUS") (pintype "bidirectional"))
      (node (ref "CONN2") (pin "2") (pinfunction "2_2") (pintype "passive"))
      (node (ref "D17") (pin "4") (pinfunction "VCC_4") (pintype "passive"))
      (node (ref "R10") (pin "2") (pinfunction "2_2") (pintype "passive"))
      (node (ref "R11") (pin "1") (pinfunction "1_1") (pintype "passive"))
      (node (ref "R13") (pin "1") (pinfunction "1_1") (pintype "passive"))
      (node (ref "R14") (pin "1") (pinfunction "1_1") (pintype "passive"))
      (node (ref "R15") (pin "1") (pinfunction "1_1") (pintype "passive"))
      (node (ref "R16") (pin "1") (pinfunction "1_1") (pintype "passive"))
      (node (ref "R17") (pin "1") (pinfunction "1_1") (pintype "passive"))
      (node (ref "R18") (pin "1") (pinfunction "1_1") (pintype "passive"))
      (node (ref "R3") (pin "1") (pinfunction "1_1") (pintype "passive"))
      (node (ref "R4") (pin "1") (pinfunction "1_1") (pintype "passive"))
      (node (ref "R8") (pin "1") (pinfunction "1_1") (pintype "passive"))
      (node (ref "R9") (pin "1") (pinfunction "1_1") (pintype "passive"))
      (node (ref "U1") (pin "14") (pinfunction "VCC_14") (pintype "power_in"))
      (node (ref "U1") (pin "2") (pinfunction "UVCC_2") (pintype "power_in"))
      (node (ref "U1") (pin "24") (pinfunction "AVCC_24") (pintype "power_in"))
      (node (ref "U1") (pin "34") (pinfunction "VCC_34") (pintype "power_in"))
      (node (ref "U1") (pin "44") (pinfunction "AVCC_44") (pintype "power_in"))
      (node (ref "U1") (pin "7") (pinfunction "VBUS_7") (pintype "power_in"))
      (node (ref "U2") (pin "7") (pinfunction "VE_7") (pintype "input"))
      (node (ref "U2") (pin "8") (pinfunction "VCC_8") (pintype "power_in"))
      (node (ref "U3") (pin "16") (pinfunction "VCC_16") (pintype "power_in"))
      (node (ref "U4") (pin "16") (pinfunction "VCC_16") (pintype "power_in"))
      (node (ref "U4") (pin "6") (pinfunction "E3_6") (pintype "input"))
      (node (ref "U7") (pin "16") (pinfunction "VCC_16") (pintype "power_in"))
      (node (ref "U7") (pin "6") (pinfunction "E3_6") (pintype "input"))
      (node (ref "U8") (pin "10") (pinfunction "COM_10") (pintype "passive"))
      (node (ref "VR1") (pin "1") (pinfunction "IN_1") (pintype "power_in"))
      (node (ref "VR1") (pin "3") (pinfunction "EN_3") (pintype "input"))
      (node (ref "VR2") (pin "1") (pinfunction "VIN_1") (pintype "passive"))
    )
    (net (code "2") (name "AREF") (class "Default")
      (node (ref "AH2") (pin "1") (pinfunction "1_1") (pintype "passive"))
      (node (ref "AH2") (pin "11") (pinfunction "11_11") (pintype "passive"))
      (node (ref "AH2") (pin "13") (pinfunction "13_13") (pintype "passive"))
      (node (ref "AH2") (pin "15") (pinfunction "15_15") (pintype "passive"))
      (node (ref "AH2") (pin "3") (pinfunction "3_3") (pintype "passive"))
      (node (ref "AH2") (pin "5") (pinfunction "5_5") (pintype "passive"))
      (node (ref "AH2") (pin "7") (pinfunction "7_7") (pintype "passive"))
      (node (ref "AH2") (pin "9") (pinfunction "9_9") (pintype "passive"))
      (node (ref "AH4") (pin "1") (pinfunction "1_1") (pintype "passive"))
      (node (ref "AH4") (pin "11") (pinfunction "11_11") (pintype "passive"))
      (node (ref "AH4") (pin "13") (pinfunction "13_13") (pintype "passive"))
      (node (ref "AH4") (pin "15") (pinfunction "15_15") (pintype "passive"))
      (node (ref "AH4") (pin "3") (pinfunction "3_3") (pintype "passive"))
      (node (ref "AH4") (pin "5") (pinfunction "5_5") (pintype "passive"))
      (node (ref "AH4") (pin "7") (pinfunction "7_7") (pintype "passive"))
      (node (ref "AH4") (pin "9") (pinfunction "9_9") (pintype "passive"))
      (node (ref "C16") (pin "1") (pinfunction "1_1") (pintype "passive"))
      (node (ref "C19") (pin "2") (pinfunction "2_2") (pintype "passive"))
      (node (ref "C20") (pin "2") (pinfunction "2_2") (pintype "passive"))
      (node (ref "C23") (pin "2") (pinfunction "2_2") (pintype "passive"))
      (node (ref "U1") (pin "42") (pinfunction "AREF_42") (pintype "bidirectional"))
      (node (ref "U5") (pin "24") (pinfunction "VCC_24") (pintype "passive"))
      (node (ref "U6") (pin "24") (pinfunction "VCC_24") (pintype "passive"))
      (node (ref "U9") (pin "14") (pinfunction "VCC_14") (pintype "passive"))
      (node (ref "VR2") (pin "3") (pinfunction "VOUT_3") (pintype "passive"))
    )
    (net (code "3") (name "A_IN_1") (class "Default")
      (node (ref "AH1") (pin "1") (pinfunction "1_1") (pintype "passive"))
      (node (ref "U5") (pin "23") (pinfunction "Y8_23") (pintype "bidirectional"))
    )
    (net (code "4") (name "A_IN_2") (class "Default")
      (node (ref "AH1") (pin "3") (pinfunction "3_3") (pintype "passive"))
      (node (ref "U5") (pin "22") (pinfunction "Y9_22") (pintype "bidirectional"))
    )
    (net (code "5") (name "A_IN_3") (class "Default")
      (node (ref "AH1") (pin "5") (pinfunction "5_5") (pintype "passive"))
      (node (ref "U5") (pin "21") (pinfunction "Y10_21") (pintype "bidirectional"))
    )
    (net (code "6") (name "A_IN_4") (class "Default")
      (node (ref "AH1") (pin "7") (pinfunction "7_7") (pintype "passive"))
      (node (ref "U5") (pin "20") (pinfunction "Y11_20") (pintype "bidirectional"))
    )
    (net (code "7") (name "A_IN_5") (class "Default")
      (node (ref "AH1") (pin "9") (pinfunction "9_9") (pintype "passive"))
      (node (ref "U5") (pin "19") (pinfunction "Y12_19") (pintype "bidirectional"))
    )
    (net (code "8") (name "A_IN_6") (class "Default")
      (node (ref "AH1") (pin "11") (pinfunction "11_11") (pintype "passive"))
      (node (ref "U5") (pin "18") (pinfunction "Y13_18") (pintype "bidirectional"))
    )
    (net (code "9") (name "A_IN_7") (class "Default")
      (node (ref "AH1") (pin "13") (pinfunction "13_13") (pintype "passive"))
      (node (ref "U5") (pin "17") (pinfunction "Y14_17") (pintype "bidirectional"))
    )
    (net (code "10") (name "A_IN_8") (class "Default")
      (node (ref "AH1") (pin "15") (pinfunction "15_15") (pintype "passive"))
      (node (ref "U5") (pin "16") (pinfunction "Y15_16") (pintype "bidirectional"))
    )
    (net (code "11") (name "A_IN_9") (class "Default")
      (node (ref "AH1") (pin "6") (pinfunction "6_6") (pintype "passive"))
      (node (ref "U5") (pin "2") (pinfunction "Y7_2") (pintype "bidirectional"))
    )
    (net (code "12") (name "A_IN_10") (class "Default")
      (node (ref "AH1") (pin "8") (pinfunction "8_8") (pintype "passive"))
      (node (ref "U5") (pin "3") (pinfunction "Y6_3") (pintype "bidirectional"))
    )
    (net (code "13") (name "A_IN_11") (class "Default")
      (node (ref "AH1") (pin "4") (pinfunction "4_4") (pintype "passive"))
      (node (ref "U5") (pin "4") (pinfunction "Y5_4") (pintype "bidirectional"))
    )
    (net (code "14") (name "A_IN_12") (class "Default")
      (node (ref "AH1") (pin "2") (pinfunction "2_2") (pintype "passive"))
      (node (ref "U5") (pin "5") (pinfunction "Y4_5") (pintype "bidirectional"))
    )
    (net (code "15") (name "A_IN_13") (class "Default")
      (node (ref "AH1") (pin "16") (pinfunction "16_16") (pintype "passive"))
      (node (ref "U5") (pin "6") (pinfunction "Y3_6") (pintype "bidirectional"))
    )
    (net (code "16") (name "A_IN_14") (class "Default")
      (node (ref "AH1") (pin "14") (pinfunction "14_14") (pintype "passive"))
      (node (ref "U5") (pin "7") (pinfunction "Y2_7") (pintype "bidirectional"))
    )
    (net (code "17") (name "A_IN_15") (class "Default")
      (node (ref "AH1") (pin "12") (pinfunction "12_12") (pintype "passive"))
      (node (ref "U5") (pin "8") (pinfunction "Y1_8") (pintype "bidirectional"))
    )
    (net (code "18") (name "A_IN_16") (class "Default")
      (node (ref "AH1") (pin "10") (pinfunction "10_10") (pintype "passive"))
      (node (ref "U5") (pin "9") (pinfunction "Y0_9") (pintype "bidirectional"))
    )
    (net (code "19") (name "A_IN_17") (class "Default")
      (node (ref "AH3") (pin "1") (pinfunction "1_1") (pintype "passive"))
      (node (ref "U6") (pin "23") (pinfunction "Y8_23") (pintype "bidirectional"))
    )
    (net (code "20") (name "A_IN_18") (class "Default")
      (node (ref "AH3") (pin "3") (pinfunction "3_3") (pintype "passive"))
      (node (ref "U6") (pin "22") (pinfunction "Y9_22") (pintype "bidirectional"))
    )
    (net (code "21") (name "A_IN_19") (class "Default")
      (node (ref "AH3") (pin "5") (pinfunction "5_5") (pintype "passive"))
      (node (ref "U6") (pin "21") (pinfunction "Y10_21") (pintype "bidirectional"))
    )
    (net (code "22") (name "A_IN_20") (class "Default")
      (node (ref "AH3") (pin "7") (pinfunction "7_7") (pintype "passive"))
      (node (ref "U6") (pin "20") (pinfunction "Y11_20") (pintype "bidirectional"))
    )
    (net (code "23") (name "A_IN_21") (class "Default")
      (node (ref "AH3") (pin "9") (pinfunction "9_9") (pintype "passive"))
      (node (ref "U6") (pin "19") (pinfunction "Y12_19") (pintype "bidirectional"))
    )
    (net (code "24") (name "A_IN_22") (class "Default")
      (node (ref "AH3") (pin "11") (pinfunction "11_11") (pintype "passive"))
      (node (ref "U6") (pin "18") (pinfunction "Y13_18") (pintype "bidirectional"))
    )
    (net (code "25") (name "A_IN_23") (class "Default")
      (node (ref "AH3") (pin "13") (pinfunction "13_13") (pintype "passive"))
      (node (ref "U6") (pin "17") (pinfunction "Y14_17") (pintype "bidirectional"))
    )
    (net (code "26") (name "A_IN_24") (class "Default")
      (node (ref "AH3") (pin "15") (pinfunction "15_15") (pintype "passive"))
      (node (ref "U6") (pin "16") (pinfunction "Y15_16") (pintype "bidirectional"))
    )
    (net (code "27") (name "A_IN_25") (class "Default")
      (node (ref "AH3") (pin "6") (pinfunction "6_6") (pintype "passive"))
      (node (ref "U6") (pin "2") (pinfunction "Y7_2") (pintype "bidirectional"))
    )
    (net (code "28") (name "A_IN_26") (class "Default")
      (node (ref "AH3") (pin "8") (pinfunction "8_8") (pintype "passive"))
      (node (ref "U6") (pin "3") (pinfunction "Y6_3") (pintype "bidirectional"))
    )
    (net (code "29") (name "A_IN_27") (class "Default")
      (node (ref "AH3") (pin "4") (pinfunction "4_4") (pintype "passive"))
      (node (ref "U6") (pin "4") (pinfunction "Y5_4") (pintype "bidirectional"))
    )
    (net (code "30") (name "A_IN_28") (class "Default")
      (node (ref "AH3") (pin "2") (pinfunction "2_2") (pintype "passive"))
      (node (ref "U6") (pin "5") (pinfunction "Y4_5") (pintype "bidirectional"))
    )
    (net (code "31") (name "A_IN_29") (class "Default")
      (node (ref "AH3") (pin "16") (pinfunction "16_16") (pintype "passive"))
      (node (ref "U6") (pin "6") (pinfunction "Y3_6") (pintype "bidirectional"))
    )
    (net (code "32") (name "A_IN_30") (class "Default")
      (node (ref "AH3") (pin "14") (pinfunction "14_14") (pintype "passive"))
      (node (ref "U6") (pin "7") (pinfunction "Y2_7") (pintype "bidirectional"))
    )
    (net (code "33") (name "A_IN_31") (class "Default")
      (node (ref "AH3") (pin "12") (pinfunction "12_12") (pintype "passive"))
      (node (ref "U6") (pin "8") (pinfunction "Y1_8") (pintype "bidirectional"))
    )
    (net (code "34") (name "A_IN_32") (class "Default")
      (node (ref "AH3") (pin "10") (pinfunction "10_10") (pintype "passive"))
      (node (ref "U6") (pin "9") (pinfunction "Y0_9") (pintype "bidirectional"))
    )
    (net (code "35") (name "BC_1") (class "Default")
      (node (ref "IH1") (pin "1") (pinfunction "1_1") (pintype "passive"))
      (node (ref "IH1") (pin "13") (pinfunction "13_13") (pintype "passive"))
      (node (ref "IH1") (pin "5") (pinfunction "5_5") (pintype "passive"))
      (node (ref "IH1") (pin "9") (pinfunction "9_9") (pintype "passive"))
      (node (ref "IH5") (pin "1") (pinfunction "1_1") (pintype "passive"))
      (node (ref "IH5") (pin "13") (pinfunction "13_13") (pintype "passive"))
      (node (ref "IH5") (pin "5") (pinfunction "5_5") (pintype "passive"))
      (node (ref "IH5") (pin "9") (pinfunction "9_9") (pintype "passive"))
      (node (ref "U4") (pin "15") (pinfunction "~{Y0}_15") (pintype "output"))
    )
    (net (code "36") (name "BC_2") (class "Default")
      (node (ref "IH1") (pin "11") (pinfunction "11_11") (pintype "passive"))
      (node (ref "IH1") (pin "15") (pinfunction "15_15") (pintype "passive"))
      (node (ref "IH1") (pin "3") (pinfunction "3_3") (pintype "passive"))
      (node (ref "IH1") (pin "7") (pinfunction "7_7") (pintype "passive"))
      (node (ref "IH5") (pin "11") (pinfunction "11_11") (pintype "passive"))
      (node (ref "IH5") (pin "15") (pinfunction "15_15") (pintype "passive"))
      (node (ref "IH5") (pin "3") (pinfunction "3_3") (pintype "passive"))
      (node (ref "IH5") (pin "7") (pinfunction "7_7") (pintype "passive"))
      (node (ref "U4") (pin "7") (pinfunction "~{Y7}_7") (pintype "output"))
    )
    (net (code "37") (name "BC_3") (class "Default")
      (node (ref "IH2") (pin "1") (pinfunction "1_1") (pintype "passive"))
      (node (ref "IH2") (pin "13") (pinfunction "13_13") (pintype "passive"))
      (node (ref "IH2") (pin "5") (pinfunction "5_5") (pintype "passive"))
      (node (ref "IH2") (pin "9") (pinfunction "9_9") (pintype "passive"))
      (node (ref "IH6") (pin "1") (pinfunction "1_1") (pintype "passive"))
      (node (ref "IH6") (pin "13") (pinfunction "13_13") (pintype "passive"))
      (node (ref "IH6") (pin "5") (pinfunction "5_5") (pintype "passive"))
      (node (ref "IH6") (pin "9") (pinfunction "9_9") (pintype "passive"))
      (node (ref "U4") (pin "13") (pinfunction "~{Y2}_13") (pintype "output"))
    )
    (net (code "38") (name "BC_4") (class "Default")
      (node (ref "IH2") (pin "11") (pinfunction "11_11") (pintype "passive"))
      (node (ref "IH2") (pin "15") (pinfunction "15_15") (pintype "passive"))
      (node (ref "IH2") (pin "3") (pinfunction "3_3") (pintype "passive"))
      (node (ref "IH2") (pin "7") (pinfunction "7_7") (pintype "passive"))
      (node (ref "IH6") (pin "11") (pinfunction "11_11") (pintype "passive"))
      (node (ref "IH6") (pin "15") (pinfunction "15_15") (pintype "passive"))
      (node (ref "IH6") (pin "3") (pinfunction "3_3") (pintype "passive"))
      (node (ref "IH6") (pin "7") (pinfunction "7_7") (pintype "passive"))
      (node (ref "U4") (pin "14") (pinfunction "~{Y1}_14") (pintype "output"))
    )
    (net (code "39") (name "BC_5") (class "Default")
      (node (ref "IH3") (pin "1") (pinfunction "1_1") (pintype "passive"))
      (node (ref "IH3") (pin "13") (pinfunction "13_13") (pintype "passive"))
      (node (ref "IH3") (pin "5") (pinfunction "5_5") (pintype "passive"))
      (node (ref "IH3") (pin "9") (pinfunction "9_9") (pintype "passive"))
      (node (ref "IH7") (pin "1") (pinfunction "1_1") (pintype "passive"))
      (node (ref "IH7") (pin "13") (pinfunction "13_13") (pintype "passive"))
      (node (ref "IH7") (pin "5") (pinfunction "5_5") (pintype "passive"))
      (node (ref "IH7") (pin "9") (pinfunction "9_9") (pintype "passive"))
      (node (ref "U4") (pin "11") (pinfunction "~{Y4}_11") (pintype "output"))
    )
    (net (code "40") (name "BC_6") (class "Default")
      (node (ref "IH3") (pin "11") (pinfunction "11_11") (pintype "passive"))
      (node (ref "IH3") (pin "15") (pinfunction "15_15") (pintype "passive"))
      (node (ref "IH3") (pin "3") (pinfunction "3_3") (pintype "passive"))
      (node (ref "IH3") (pin "7") (pinfunction "7_7") (pintype "passive"))
      (node (ref "IH7") (pin "11") (pinfunction "11_11") (pintype "passive"))
      (node (ref "IH7") (pin "15") (pinfunction "15_15") (pintype "passive"))
      (node (ref "IH7") (pin "3") (pinfunction "3_3") (pintype "passive"))
      (node (ref "IH7") (pin "7") (pinfunction "7_7") (pintype "passive"))
      (node (ref "U4") (pin "12") (pinfunction "~{Y3}_12") (pintype "output"))
    )
    (net (code "41") (name "BC_7") (class "Default")
      (node (ref "IH4") (pin "1") (pinfunction "1_1") (pintype "passive"))
      (node (ref "IH4") (pin "13") (pinfunction "13_13") (pintype "passive"))
      (node (ref "IH4") (pin "5") (pinfunction "5_5") (pintype "passive"))
      (node (ref "IH4") (pin "9") (pinfunction "9_9") (pintype "passive"))
      (node (ref "IH8") (pin "1") (pinfunction "1_1") (pintype "passive"))
      (node (ref "IH8") (pin "13") (pinfunction "13_13") (pintype "passive"))
      (node (ref "IH8") (pin "5") (pinfunction "5_5") (pintype "passive"))
      (node (ref "IH8") (pin "9") (pinfunction "9_9") (pintype "passive"))
      (node (ref "U4") (pin "10") (pinfunction "~{Y5}_10") (pintype "output"))
    )
    (net (code "42") (name "BC_8") (class "Default")
      (node (ref "IH4") (pin "11") (pinfunction "11_11") (pintype "passive"))
      (node (ref "IH4") (pin "15") (pinfunction "15_15") (pintype "passive"))
      (node (ref "IH4") (pin "3") (pinfunction "3_3") (pintype "passive"))
      (node (ref "IH4") (pin "7") (pinfunction "7_7") (pintype "passive"))
      (node (ref "IH8") (pin "11") (pinfunction "11_11") (pintype "passive"))
      (node (ref "IH8") (pin "15") (pinfunction "15_15") (pintype "passive"))
      (node (ref "IH8") (pin "3") (pinfunction "3_3") (pintype "passive"))
      (node (ref "IH8") (pin "7") (pinfunction "7_7") (pintype "passive"))
      (node (ref "U4") (pin "9") (pinfunction "~{Y6}_9") (pintype "output"))
    )
    (net (code "43") (name "BR_1") (class "Default")
      (node (ref "D1") (pin "3") (pinfunction "3_3") (pintype "passive"))
      (node (ref "D2") (pin "3") (pinfunction "3_3") (pintype "passive"))
      (node (ref "D3") (pin "3") (pinfunction "3_3") (pintype "passive"))
      (node (ref "D4") (pin "3") (pinfunction "3_3") (pintype "passive"))
      (node (ref "R9") (pin "2") (pinfunction "2_2") (pintype "passive"))
      (node (ref "U3") (pin "11") (pinfunction "D0_11") (pintype "input"))
    )
    (net (code "44") (name "BR_2") (class "Default")
      (node (ref "D5") (pin "3") (pinfunction "3_3") (pintype "passive"))
      (node (ref "D6") (pin "3") (pinfunction "3_3") (pintype "passive"))
      (node (ref "D7") (pin "3") (pinfunction "3_3") (pintype "passive"))
      (node (ref "D8") (pin "3") (pinfunction "3_3") (pintype "passive"))
      (node (ref "R11") (pin "2") (pinfunction "2_2") (pintype "passive"))
      (node (ref "U3") (pin "12") (pinfunction "D1_12") (pintype "input"))
    )
    (net (code "45") (name "BR_3") (class "Default")
      (node (ref "D10") (pin "3") (pinfunction "3_3") (pintype "passive"))
      (node (ref "D11") (pin "3") (pinfunction "3_3") (pintype "passive"))
      (node (ref "D12") (pin "3") (pinfunction "3_3") (pintype "passive"))
      (node (ref "D9") (pin "3") (pinfunction "3_3") (pintype "passive"))
      (node (ref "R13") (pin "2") (pinfunction "2_2") (pintype "passive"))
      (node (ref "U3") (pin "13") (pinfunction "D2_13") (pintype "input"))
    )
    (net (code "46") (name "BR_4") (class "Default")
      (node (ref "D13") (pin "3") (pinfunction "3_3") (pintype "passive"))
      (node (ref "D14") (pin "3") (pinfunction "3_3") (pintype "passive"))
      (node (ref "D15") (pin "3") (pinfunction "3_3") (pintype "passive"))
      (node (ref "D16") (pin "3") (pinfunction "3_3") (pintype "passive"))
      (node (ref "R14") (pin "2") (pinfunction "2_2") (pintype "passive"))
      (node (ref "U3") (pin "14") (pinfunction "D3_14") (pintype "input"))
    )
    (net (code "47") (name "BR_5") (class "Default")
      (node (ref "D30") (pin "3") (pinfunction "3_3") (pintype "passive"))
      (node (ref "D31") (pin "3") (pinfunction "3_3") (pintype "passive"))
      (node (ref "D32") (pin "3") (pinfunction "3_3") (pintype "passive"))
      (node (ref "D33") (pin "3") (pinfunction "3_3") (pintype "passive"))
      (node (ref "R15") (pin "2") (pinfunction "2_2") (pintype "passive"))
      (node (ref "U3") (pin "3") (pinfunction "D4_3") (pintype "input"))
    )
    (net (code "48") (name "BR_6") (class "Default")
      (node (ref "D26") (pin "3") (pinfunction "3_3") (pintype "passive"))
      (node (ref "D27") (pin "3") (pinfunction "3_3") (pintype "passive"))
      (node (ref "D28") (pin "3") (pinfunction "3_3") (pintype "passive"))
      (node (ref "D29") (pin "3") (pinfunction "3_3") (pintype "passive"))
      (node (ref "R16") (pin "2") (pinfunction "2_2") (pintype "passive"))
      (node (ref "U3") (pin "4") (pinfunction "D5_4") (pintype "input"))
    )
    (net (code "49") (name "BR_7") (class "Default")
      (node (ref "D22") (pin "3") (pinfunction "3_3") (pintype "passive"))
      (node (ref "D23") (pin "3") (pinfunction "3_3") (pintype "passive"))
      (node (ref "D24") (pin "3") (pinfunction "3_3") (pintype "passive"))
      (node (ref "D25") (pin "3") (pinfunction "3_3") (pintype "passive"))
      (node (ref "R17") (pin "2") (pinfunction "2_2") (pintype "passive"))
      (node (ref "U3") (pin "5") (pinfunction "D6_5") (pintype "input"))
    )
    (net (code "50") (name "BR_8") (class "Default")
      (node (ref "D18") (pin "3") (pinfunction "3_3") (pintype "passive"))
      (node (ref "D19") (pin "3") (pinfunction "3_3") (pintype "passive"))
      (node (ref "D20") (pin "3") (pinfunction "3_3") (pintype "passive"))
      (node (ref "D21") (pin "3") (pinfunction "3_3") (pintype "passive"))
      (node (ref "R18") (pin "2") (pinfunction "2_2") (pintype "passive"))
      (node (ref "U3") (pin "6") (pinfunction "D7_6") (pintype "input"))
    )
    (net (code "51") (name "D+") (class "Default")
      (node (ref "R1") (pin "2") (pinfunction "2_2") (pintype "passive"))
      (node (ref "U1") (pin "4") (pinfunction "D+_4") (pintype "bidirectional"))
    )
    (net (code "52") (name "D+X") (class "Default")
      (node (ref "CONN1") (pin "D+") (pinfunction "D+_D+") (pintype "bidirectional"))
      (node (ref "D17") (pin "3") (pinfunction "I/O2_3") (pintype "passive"))
      (node (ref "R1") (pin "1") (pinfunction "1_1") (pintype "passive"))
    )
    (net (code "53") (name "D-") (class "Default")
      (node (ref "R2") (pin "1") (pinfunction "1_1") (pintype "passive"))
      (node (ref "U1") (pin "3") (pinfunction "D-_3") (pintype "bidirectional"))
    )
    (net (code "54") (name "D-X") (class "Default")
      (node (ref "CONN1") (pin "D-") (pinfunction "D-_D-") (pintype "bidirectional"))
      (node (ref "D17") (pin "2") (pinfunction "I/O1_2") (pintype "passive"))
      (node (ref "R2") (pin "2") (pinfunction "2_2") (pintype "passive"))
    )
    (net (code "55") (name "DEC_BM_A0") (class "Default")
      (node (ref "U1") (pin "28") (pinfunction "PB4(PCINT4/ADC11)_28") (pintype "bidirectional"))
      (node (ref "U4") (pin "1") (pinfunction "A0_1") (pintype "input"))
    )
    (net (code "56") (name "DEC_BM_A1") (class "Default")
      (node (ref "U1") (pin "26") (pinfunction "PD6(T1/~{OC4D}/ADC9)_26") (pintype "bidirectional"))
      (node (ref "U4") (pin "2") (pinfunction "A1_2") (pintype "input"))
    )
    (net (code "57") (name "DEC_BM_A2") (class "Default")
      (node (ref "U1") (pin "25") (pinfunction "PD4(ICP1/ADC8)_25") (pintype "bidirectional"))
      (node (ref "U4") (pin "3") (pinfunction "A2_3") (pintype "input"))
    )
    (net (code "58") (name "DEC_LM_A0{slash}SCK") (class "Default")
      (node (ref "CONN2") (pin "3") (pinfunction "3_3") (pintype "passive"))
      (node (ref "U1") (pin "9") (pinfunction "PB1(PCINT1/SCLK)_9") (pintype "bidirectional"))
      (node (ref "U7") (pin "1") (pinfunction "A0_1") (pintype "input"))
    )
    (net (code "59") (name "DEC_LM_A1{slash}MOSI") (class "Default")
      (node (ref "CONN2") (pin "4") (pinfunction "4_4") (pintype "passive"))
      (node (ref "CONN5") (pin "1") (pinfunction "1_1") (pintype "passive"))
      (node (ref "U1") (pin "10") (pinfunction "PB2(PDI/PCINT2/MOSI)_10") (pintype "bidirectional"))
      (node (ref "U7") (pin "2") (pinfunction "A1_2") (pintype "input"))
    )
    (net (code "60") (name "DEC_LM_A2{slash}MISO") (class "Default")
      (node (ref "CONN2") (pin "1") (pinfunction "1_1") (pintype "passive"))
      (node (ref "U1") (pin "11") (pinfunction "PB3(PDO/PCINT3/MISO)_11") (pintype "bidirectional"))
      (node (ref "U7") (pin "3") (pinfunction "A2_3") (pintype "input"))
    )
    (net (code "61") (name "GND") (class "Default")
      (node (ref "AH2") (pin "10") (pinfunction "10_10") (pintype "passive"))
      (node (ref "AH2") (pin "12") (pinfunction "12_12") (pintype "passive"))
      (node (ref "AH2") (pin "14") (pinfunction "14_14") (pintype "passive"))
      (node (ref "AH2") (pin "16") (pinfunction "16_16") (pintype "passive"))
      (node (ref "AH2") (pin "2") (pinfunction "2_2") (pintype "passive"))
      (node (ref "AH2") (pin "4") (pinfunction "4_4") (pintype "passive"))
      (node (ref "AH2") (pin "6") (pinfunction "6_6") (pintype "passive"))
      (node (ref "AH2") (pin "8") (pinfunction "8_8") (pintype "passive"))
      (node (ref "AH4") (pin "10") (pinfunction "10_10") (pintype "passive"))
      (node (ref "AH4") (pin "12") (pinfunction "12_12") (pintype "passive"))
      (node (ref "AH4") (pin "14") (pinfunction "14_14") (pintype "passive"))
      (node (ref "AH4") (pin "16") (pinfunction "16_16") (pintype "passive"))
      (node (ref "AH4") (pin "2") (pinfunction "2_2") (pintype "passive"))
      (node (ref "AH4") (pin "4") (pinfunction "4_4") (pintype "passive"))
      (node (ref "AH4") (pin "6") (pinfunction "6_6") (pintype "passive"))
      (node (ref "AH4") (pin "8") (pinfunction "8_8") (pintype "passive"))
      (node (ref "C1") (pin "2") (pinfunction "2_2") (pintype "passive"))
      (node (ref "C10") (pin "2") (pinfunction "2_2") (pintype "passive"))
      (node (ref "C11") (pin "2") (pinfunction "2_2") (pintype "passive"))
      (node (ref "C12") (pin "2") (pinfunction "2_2") (pintype "passive"))
      (node (ref "C13") (pin "2") (pinfunction "2_2") (pintype "passive"))
      (node (ref "C14") (pin "2") (pinfunction "2_2") (pintype "passive"))
      (node (ref "C15") (pin "1") (pinfunction "1_1") (pintype "passive"))
      (node (ref "C16") (pin "2") (pinfunction "2_2") (pintype "passive"))
      (node (ref "C17") (pin "1") (pinfunction "1_1") (pintype "passive"))
      (node (ref "C18") (pin "1") (pinfunction "1_1") (pintype "passive"))
      (node (ref "C19") (pin "1") (pinfunction "1_1") (pintype "passive"))
      (node (ref "C2") (pin "2") (pinfunction "2_2") (pintype "passive"))
      (node (ref "C20") (pin "1") (pinfunction "1_1") (pintype "passive"))
      (node (ref "C21") (pin "2") (pinfunction "2_2") (pintype "passive"))
      (node (ref "C22") (pin "2") (pinfunction "2_2") (pintype "passive"))
      (node (ref "C23") (pin "1") (pinfunction "1_1") (pintype "passive"))
      (node (ref "C3") (pin "2") (pinfunction "2_2") (pintype "passive"))
      (node (ref "C4") (pin "1") (pinfunction "1_1") (pintype "passive"))
      (node (ref "C5") (pin "2") (pinfunction "2_2") (pintype "passive"))
      (node (ref "C6") (pin "-") (pinfunction "-_-") (pintype "passive"))
      (node (ref "C7") (pin "2") (pinfunction "2_2") (pintype "passive"))
      (node (ref "C8") (pin "2") (pinfunction "2_2") (pintype "passive"))
      (node (ref "C9") (pin "2") (pinfunction "2_2") (pintype "passive"))
      (node (ref "CONN1") (pin "GND") (pinfunction "GND_GND") (pintype "bidirectional"))
      (node (ref "CONN2") (pin "6") (pinfunction "6_6") (pintype "passive"))
      (node (ref "CONN4") (pin "2") (pinfunction "2_2") (pintype "passive"))
      (node (ref "CONN5") (pin "2") (pinfunction "2_2") (pintype "passive"))
      (node (ref "D17") (pin "1") (pinfunction "GND_1") (pintype "passive"))
      (node (ref "D35") (pin "C") (pinfunction "C_C") (pintype "passive"))
      (node (ref "D36") (pin "C") (pinfunction "C_C") (pintype "passive"))
      (node (ref "D37") (pin "C") (pinfunction "C_C") (pintype "passive"))
      (node (ref "L1") (pin "1") (pinfunction "1_1") (pintype "passive"))
      (node (ref "U1") (pin "15") (pinfunction "GND_15") (pintype "power_in"))
      (node (ref "U1") (pin "23") (pinfunction "GND_23") (pintype "power_in"))
      (node (ref "U1") (pin "35") (pinfunction "GND_35") (pintype "power_in"))
      (node (ref "U1") (pin "43") (pinfunction "GND_43") (pintype "power_in"))
      (node (ref "U1") (pin "5") (pinfunction "UGND_5") (pintype "power_in"))
      (node (ref "U2") (pin "5") (pinfunction "GND_5") (pintype "power_in"))
      (node (ref "U3") (pin "15") (pinfunction "~{CE}_15") (pintype "input"))
      (node (ref "U3") (pin "8") (pinfunction "GND_8") (pintype "power_in"))
      (node (ref "U4") (pin "4") (pinfunction "~{E1}_4") (pintype "input"))
      (node (ref "U4") (pin "5") (pinfunction "~{E2}_5") (pintype "input"))
      (node (ref "U4") (pin "8") (pinfunction "GND_8") (pintype "power_in"))
      (node (ref "U5") (pin "12") (pinfunction "GND_12") (pintype "passive"))
      (node (ref "U5") (pin "15") (pinfunction "~{E}_15") (pintype "input"))
      (node (ref "U6") (pin "12") (pinfunction "GND_12") (pintype "passive"))
      (node (ref "U6") (pin "15") (pinfunction "~{E}_15") (pintype "input"))
      (node (ref "U7") (pin "4") (pinfunction "~{E1}_4") (pintype "input"))
      (node (ref "U7") (pin "5") (pinfunction "~{E2}_5") (pintype "input"))
      (node (ref "U7") (pin "8") (pinfunction "GND_8") (pintype "power_in"))
      (node (ref "U8") (pin "9") (pinfunction "GND_9") (pintype "power_in"))
      (node (ref "U9") (pin "1") (pinfunction "1~{(OE})_1") (pintype "bidirectional"))
      (node (ref "U9") (pin "10") (pinfunction "3~{(OE})_10") (pintype "bidirectional"))
      (node (ref "U9") (pin "13") (pinfunction "4~{(OE})_13") (pintype "bidirectional"))
      (node (ref "U9") (pin "4") (pinfunction "2~{(OE})_4") (pintype "bidirectional"))
      (node (ref "U9") (pin "7") (pinfunction "VEE_7") (pintype "passive"))
      (node (ref "VR1") (pin "2") (pinfunction "GND_2") (pintype "power_in"))
      (node (ref "VR2") (pin "2") (pinfunction "GND_2") (pintype "passive"))
      (node (ref "VR2") (pin "4") (pinfunction "GND_4") (pintype "passive"))
    )
    (net (code "62") (name "LC_1") (class "Default")
      (node (ref "OH1") (pin "10") (pinfunction "10_10") (pintype "passive"))
      (node (ref "OH1") (pin "12") (pinfunction "12_12") (pintype "passive"))
      (node (ref "OH1") (pin "2") (pinfunction "2_2") (pintype "passive"))
      (node (ref "OH1") (pin "4") (pinfunction "4_4") (pintype "passive"))
      (node (ref "OH1") (pin "6") (pinfunction "6_6") (pintype "passive"))
      (node (ref "OH1") (pin "8") (pinfunction "8_8") (pintype "passive"))
      (node (ref "U8") (pin "18") (pinfunction "1C_18") (pintype "open_collector"))
    )
    (net (code "63") (name "LC_2") (class "Default")
      (node (ref "OH2") (pin "10") (pinfunction "10_10") (pintype "passive"))
      (node (ref "OH2") (pin "12") (pinfunction "12_12") (pintype "passive"))
      (node (ref "OH2") (pin "2") (pinfunction "2_2") (pintype "passive"))
      (node (ref "OH2") (pin "4") (pinfunction "4_4") (pintype "passive"))
      (node (ref "OH2") (pin "6") (pinfunction "6_6") (pintype "passive"))
      (node (ref "OH2") (pin "8") (pinfunction "8_8") (pintype "passive"))
      (node (ref "U8") (pin "17") (pinfunction "2C_17") (pintype "open_collector"))
    )
    (net (code "64") (name "LC_3") (class "Default")
      (node (ref "OH3") (pin "10") (pinfunction "10_10") (pintype "passive"))
      (node (ref "OH3") (pin "12") (pinfunction "12_12") (pintype "passive"))
      (node (ref "OH3") (pin "2") (pinfunction "2_2") (pintype "passive"))
      (node (ref "OH3") (pin "4") (pinfunction "4_4") (pintype "passive"))
      (node (ref "OH3") (pin "6") (pinfunction "6_6") (pintype "passive"))
      (node (ref "OH3") (pin "8") (pinfunction "8_8") (pintype "passive"))
      (node (ref "U8") (pin "16") (pinfunction "3C_16") (pintype "open_collector"))
    )
    (net (code "65") (name "LC_4") (class "Default")
      (node (ref "OH4") (pin "10") (pinfunction "10_10") (pintype "passive"))
      (node (ref "OH4") (pin "12") (pinfunction "12_12") (pintype "passive"))
      (node (ref "OH4") (pin "2") (pinfunction "2_2") (pintype "passive"))
      (node (ref "OH4") (pin "4") (pinfunction "4_4") (pintype "passive"))
      (node (ref "OH4") (pin "6") (pinfunction "6_6") (pintype "passive"))
      (node (ref "OH4") (pin "8") (pinfunction "8_8") (pintype "passive"))
      (node (ref "U8") (pin "15") (pinfunction "4C_15") (pintype "open_collector"))
    )
    (net (code "66") (name "LC_5") (class "Default")
      (node (ref "OH5") (pin "10") (pinfunction "10_10") (pintype "passive"))
      (node (ref "OH5") (pin "12") (pinfunction "12_12") (pintype "passive"))
      (node (ref "OH5") (pin "2") (pinfunction "2_2") (pintype "passive"))
      (node (ref "OH5") (pin "4") (pinfunction "4_4") (pintype "passive"))
      (node (ref "OH5") (pin "6") (pinfunction "6_6") (pintype "passive"))
      (node (ref "OH5") (pin "8") (pinfunction "8_8") (pintype "passive"))
      (node (ref "U8") (pin "14") (pinfunction "5C_14") (pintype "open_collector"))
    )
    (net (code "67") (name "LC_6") (class "Default")
      (node (ref "OH6") (pin "10") (pinfunction "10_10") (pintype "passive"))
      (node (ref "OH6") (pin "12") (pinfunction "12_12") (pintype "passive"))
      (node (ref "OH6") (pin "2") (pinfunction "2_2") (pintype "passive"))
      (node (ref "OH6") (pin "4") (pinfunction "4_4") (pintype "passive"))
      (node (ref "OH6") (pin "6") (pinfunction "6_6") (pintype "passive"))
      (node (ref "OH6") (pin "8") (pinfunction "8_8") (pintype "passive"))
      (node (ref "U8") (pin "13") (pinfunction "6C_13") (pintype "open_collector"))
    )
    (net (code "68") (name "LC_7") (class "Default")
      (node (ref "OH7") (pin "10") (pinfunction "10_10") (pintype "passive"))
      (node (ref "OH7") (pin "12") (pinfunction "12_12") (pintype "passive"))
      (node (ref "OH7") (pin "2") (pinfunction "2_2") (pintype "passive"))
      (node (ref "OH7") (pin "4") (pinfunction "4_4") (pintype "passive"))
      (node (ref "OH7") (pin "6") (pinfunction "6_6") (pintype "passive"))
      (node (ref "OH7") (pin "8") (pinfunction "8_8") (pintype "passive"))
      (node (ref "U8") (pin "12") (pinfunction "7C_12") (pintype "open_collector"))
    )
    (net (code "69") (name "LC_8") (class "Default")
      (node (ref "OH8") (pin "10") (pinfunction "10_10") (pintype "passive"))
      (node (ref "OH8") (pin "12") (pinfunction "12_12") (pintype "passive"))
      (node (ref "OH8") (pin "2") (pinfunction "2_2") (pintype "passive"))
      (node (ref "OH8") (pin "4") (pinfunction "4_4") (pintype "passive"))
      (node (ref "OH8") (pin "6") (pinfunction "6_6") (pintype "passive"))
      (node (ref "OH8") (pin "8") (pinfunction "8_8") (pintype "passive"))
      (node (ref "U8") (pin "11") (pinfunction "8C_11") (pintype "open_collector"))
    )
    (net (code "70") (name "LEDS_VCC") (class "Default")
      (node (ref "C13") (pin "1") (pinfunction "1_1") (pintype "passive"))
      (node (ref "Q1") (pin "2") (pinfunction "S2_2") (pintype "bidirectional"))
      (node (ref "Q1") (pin "5") (pinfunction "S1_5") (pintype "bidirectional"))
      (node (ref "Q2") (pin "2") (pinfunction "S2_2") (pintype "bidirectional"))
      (node (ref "Q2") (pin "5") (pinfunction "S1_5") (pintype "bidirectional"))
      (node (ref "Q3") (pin "2") (pinfunction "S2_2") (pintype "bidirectional"))
      (node (ref "Q3") (pin "5") (pinfunction "S1_5") (pintype "bidirectional"))
      (node (ref "R19") (pin "1") (pinfunction "1_1") (pintype "passive"))
      (node (ref "R21") (pin "1") (pinfunction "1_1") (pintype "passive"))
      (node (ref "R23") (pin "1") (pinfunction "1_1") (pintype "passive"))
      (node (ref "R25") (pin "1") (pinfunction "1_1") (pintype "passive"))
      (node (ref "R27") (pin "1") (pinfunction "1_1") (pintype "passive"))
      (node (ref "R29") (pin "1") (pinfunction "1_1") (pintype "passive"))
      (node (ref "VR1") (pin "5") (pinfunction "OUT_5") (pintype "power_in"))
    )
    (net (code "71") (name "LR_1_MI") (class "Default")
      (node (ref "Q1") (pin "1") (pinfunction "G1_1") (pintype "bidirectional"))
      (node (ref "R19") (pin "2") (pinfunction "2_2") (pintype "passive"))
      (node (ref "U1") (pin "12") (pinfunction "PB7(PCINT7/OC0A/OC1C/~{RTS})_12") (pintype "bidirectional"))
    )
    (net (code "72") (name "LR_1_MO") (class "Default")
      (node (ref "OH1") (pin "1") (pinfunction "1_1") (pintype "passive"))
      (node (ref "OH2") (pin "1") (pinfunction "1_1") (pintype "passive"))
      (node (ref "OH3") (pin "1") (pinfunction "1_1") (pintype "passive"))
      (node (ref "OH4") (pin "1") (pinfunction "1_1") (pintype "passive"))
      (node (ref "OH5") (pin "1") (pinfunction "1_1") (pintype "passive"))
      (node (ref "OH6") (pin "1") (pinfunction "1_1") (pintype "passive"))
      (node (ref "OH7") (pin "1") (pinfunction "1_1") (pintype "passive"))
      (node (ref "OH8") (pin "1") (pinfunction "1_1") (pintype "passive"))
      (node (ref "R20") (pin "1") (pinfunction "1_1") (pintype "passive"))
    )
    (net (code "73") (name "LR_2_MI") (class "Default")
      (node (ref "Q1") (pin "3") (pinfunction "G2_3") (pintype "bidirectional"))
      (node (ref "R21") (pin "2") (pinfunction "2_2") (pintype "passive"))
      (node (ref "U1") (pin "27") (pinfunction "PD7(T0/OC4D/ADC10)_27") (pintype "bidirectional"))
    )
    (net (code "74") (name "LR_2_MO") (class "Default")
      (node (ref "OH1") (pin "3") (pinfunction "3_3") (pintype "passive"))
      (node (ref "OH2") (pin "3") (pinfunction "3_3") (pintype "passive"))
      (node (ref "OH3") (pin "3") (pinfunction "3_3") (pintype "passive"))
      (node (ref "OH4") (pin "3") (pinfunction "3_3") (pintype "passive"))
      (node (ref "OH5") (pin "3") (pinfunction "3_3") (pintype "passive"))
      (node (ref "OH6") (pin "3") (pinfunction "3_3") (pintype "passive"))
      (node (ref "OH7") (pin "3") (pinfunction "3_3") (pintype "passive"))
      (node (ref "OH8") (pin "3") (pinfunction "3_3") (pintype "passive"))
      (node (ref "R22") (pin "2") (pinfunction "2_2") (pintype "passive"))
    )
    (net (code "75") (name "LR_3_MI") (class "Default")
      (node (ref "Q3") (pin "1") (pinfunction "G1_1") (pintype "bidirectional"))
      (node (ref "R27") (pin "2") (pinfunction "2_2") (pintype "passive"))
      (node (ref "U1") (pin "29") (pinfunction "PB5(PCINT5/OC1A/~{OC4B}/ADC12)_29") (pintype "bidirectional"))
    )
    (net (code "76") (name "LR_3_MO") (class "Default")
      (node (ref "OH1") (pin "5") (pinfunction "5_5") (pintype "passive"))
      (node (ref "OH2") (pin "5") (pinfunction "5_5") (pintype "passive"))
      (node (ref "OH3") (pin "5") (pinfunction "5_5") (pintype "passive"))
      (node (ref "OH4") (pin "5") (pinfunction "5_5") (pintype "passive"))
      (node (ref "OH5") (pin "5") (pinfunction "5_5") (pintype "passive"))
      (node (ref "OH6") (pin "5") (pinfunction "5_5") (pintype "passive"))
      (node (ref "OH7") (pin "5") (pinfunction "5_5") (pintype "passive"))
      (node (ref "OH8") (pin "5") (pinfunction "5_5") (pintype "passive"))
      (node (ref "R28") (pin "1") (pinfunction "1_1") (pintype "passive"))
    )
    (net (code "77") (name "LR_4_MI") (class "Default")
      (node (ref "Q2") (pin "3") (pinfunction "G2_3") (pintype "bidirectional"))
      (node (ref "R25") (pin "2") (pinfunction "2_2") (pintype "passive"))
      (node (ref "U1") (pin "32") (pinfunction "PC7(ICP3/CLK0/OC4A)_32") (pintype "bidirectional"))
    )
    (net (code "78") (name "LR_4_MO") (class "Default")
      (node (ref "OH1") (pin "7") (pinfunction "7_7") (pintype "passive"))
      (node (ref "OH2") (pin "7") (pinfunction "7_7") (pintype "passive"))
      (node (ref "OH3") (pin "7") (pinfunction "7_7") (pintype "passive"))
      (node (ref "OH4") (pin "7") (pinfunction "7_7") (pintype "passive"))
      (node (ref "OH5") (pin "7") (pinfunction "7_7") (pintype "passive"))
      (node (ref "OH6") (pin "7") (pinfunction "7_7") (pintype "passive"))
      (node (ref "OH7") (pin "7") (pinfunction "7_7") (pintype "passive"))
      (node (ref "OH8") (pin "7") (pinfunction "7_7") (pintype "passive"))
      (node (ref "R26") (pin "1") (pinfunction "1_1") (pintype "passive"))
    )
    (net (code "79") (name "LR_5_MI") (class "Default")
      (node (ref "Q2") (pin "1") (pinfunction "G1_1") (pintype "bidirectional"))
      (node (ref "R23") (pin "2") (pinfunction "2_2") (pintype "passive"))
      (node (ref "U1") (pin "31") (pinfunction "PC6(OC3A/~{OC4A})_31") (pintype "bidirectional"))
    )
    (net (code "80") (name "LR_5_MO") (class "Default")
      (node (ref "OH1") (pin "9") (pinfunction "9_9") (pintype "passive"))
      (node (ref "OH2") (pin "9") (pinfunction "9_9") (pintype "passive"))
      (node (ref "OH3") (pin "9") (pinfunction "9_9") (pintype "passive"))
      (node (ref "OH4") (pin "9") (pinfunction "9_9") (pintype "passive"))
      (node (ref "OH5") (pin "9") (pinfunction "9_9") (pintype "passive"))
      (node (ref "OH6") (pin "9") (pinfunction "9_9") (pintype "passive"))
      (node (ref "OH7") (pin "9") (pinfunction "9_9") (pintype "passive"))
      (node (ref "OH8") (pin "9") (pinfunction "9_9") (pintype "passive"))
      (node (ref "R24") (pin "1") (pinfunction "1_1") (pintype "passive"))
    )
    (net (code "81") (name "LR_6_MI") (class "Default")
      (node (ref "Q3") (pin "3") (pinfunction "G2_3") (pintype "bidirectional"))
      (node (ref "R29") (pin "2") (pinfunction "2_2") (pintype "passive"))
      (node (ref "U1") (pin "30") (pinfunction "PB6(PCINT6/OC1B/OC4B/ADC13)_30") (pintype "bidirectional"))
    )
    (net (code "82") (name "LR_6_MO") (class "Default")
      (node (ref "OH1") (pin "11") (pinfunction "11_11") (pintype "passive"))
      (node (ref "OH2") (pin "11") (pinfunction "11_11") (pintype "passive"))
      (node (ref "OH3") (pin "11") (pinfunction "11_11") (pintype "passive"))
      (node (ref "OH4") (pin "11") (pinfunction "11_11") (pintype "passive"))
      (node (ref "OH5") (pin "11") (pinfunction "11_11") (pintype "passive"))
      (node (ref "OH6") (pin "11") (pinfunction "11_11") (pintype "passive"))
      (node (ref "OH7") (pin "11") (pinfunction "11_11") (pintype "passive"))
      (node (ref "OH8") (pin "11") (pinfunction "11_11") (pintype "passive"))
      (node (ref "R30") (pin "1") (pinfunction "1_1") (pintype "passive"))
    )
    (net (code "83") (name "MIDI_IN") (class "Default")
      (node (ref "R4") (pin "2") (pinfunction "2_2") (pintype "passive"))
      (node (ref "U1") (pin "20") (pinfunction "PD2(RXD1/INT2)_20") (pintype "bidirectional"))
      (node (ref "U2") (pin "6") (pinfunction "VO_6") (pintype "output"))
    )
    (net (code "84") (name "MIDI_IN_LED") (class "Default")
      (node (ref "R7") (pin "2") (pinfunction "2_2") (pintype "passive"))
      (node (ref "U1") (pin "1") (pinfunction "PE6(INT6/AIN0)_1") (pintype "bidirectional"))
    )
    (net (code "85") (name "MIDI_OUT") (class "Default")
      (node (ref "R12") (pin "2") (pinfunction "2_2") (pintype "passive"))
      (node (ref "U1") (pin "21") (pinfunction "PD3(TXD1/INT3)_21") (pintype "bidirectional"))
    )
    (net (code "86") (name "MIDI_OUT_LED") (class "Default")
      (node (ref "R6") (pin "2") (pinfunction "2_2") (pintype "passive"))
      (node (ref "U1") (pin "33") (pinfunction "PE2(~{HWB})_33") (pintype "bidirectional"))
    )
    (net (code "87") (name "MUX_COMMON_1") (class "Default")
      (node (ref "U1") (pin "41") (pinfunction "PF0(ADC0)_41") (pintype "bidirectional"))
      (node (ref "U5") (pin "1") (pinfunction "Z_1") (pintype "bidirectional"))
    )
    (net (code "88") (name "MUX_COMMON_2") (class "Default")
      (node (ref "U1") (pin "40") (pinfunction "PF1(ADC1)_40") (pintype "bidirectional"))
      (node (ref "U6") (pin "1") (pinfunction "Z_1") (pintype "bidirectional"))
    )
    (net (code "89") (name "MUX_S0_3V3") (class "Default")
      (node (ref "U5") (pin "10") (pinfunction "S0_10") (pintype "input"))
      (node (ref "U6") (pin "10") (pinfunction "S0_10") (pintype "input"))
      (node (ref "U9") (pin "3") (pinfunction "1Y_3") (pintype "bidirectional"))
    )
    (net (code "90") (name "MUX_S0_5V") (class "Default")
      (node (ref "U1") (pin "38") (pinfunction "PF5(ADC5/TMS)_38") (pintype "bidirectional"))
      (node (ref "U9") (pin "2") (pinfunction "1A_2") (pintype "bidirectional"))
    )
    (net (code "91") (name "MUX_S1_3V3") (class "Default")
      (node (ref "U5") (pin "11") (pinfunction "S1_11") (pintype "input"))
      (node (ref "U6") (pin "11") (pinfunction "S1_11") (pintype "input"))
      (node (ref "U9") (pin "8") (pinfunction "3Y_8") (pintype "bidirectional"))
    )
    (net (code "92") (name "MUX_S1_5V") (class "Default")
      (node (ref "U1") (pin "36") (pinfunction "PF7(ADC7/TDI)_36") (pintype "bidirectional"))
      (node (ref "U9") (pin "9") (pinfunction "3A_9") (pintype "bidirectional"))
    )
    (net (code "93") (name "MUX_S2_3V3") (class "Default")
      (node (ref "U5") (pin "14") (pinfunction "S2_14") (pintype "input"))
      (node (ref "U6") (pin "14") (pinfunction "S2_14") (pintype "input"))
      (node (ref "U9") (pin "6") (pinfunction "2Y_6") (pintype "bidirectional"))
    )
    (net (code "94") (name "MUX_S2_5V") (class "Default")
      (node (ref "U1") (pin "39") (pinfunction "PF4(ADC4/TCK)_39") (pintype "bidirectional"))
      (node (ref "U9") (pin "5") (pinfunction "2A_5") (pintype "bidirectional"))
    )
    (net (code "95") (name "MUX_S3_3V3") (class "Default")
      (node (ref "U5") (pin "13") (pinfunction "S3_13") (pintype "input"))
      (node (ref "U6") (pin "13") (pinfunction "S3_13") (pintype "input"))
      (node (ref "U9") (pin "11") (pinfunction "4Y_11") (pintype "bidirectional"))
    )
    (net (code "96") (name "MUX_S3_5V") (class "Default")
      (node (ref "U1") (pin "37") (pinfunction "PF6(ADC6/TDO)_37") (pintype "bidirectional"))
      (node (ref "U9") (pin "12") (pinfunction "4A_12") (pintype "bidirectional"))
    )
    (net (code "97") (name "Net-(CONN3-Pad4)") (class "Default")
      (node (ref "CONN3") (pin "4") (pinfunction "4_4") (pintype "bidirectional"))
      (node (ref "R5") (pin "1") (pinfunction "1_1") (pintype "passive"))
    )
    (net (code "98") (name "Net-(CONN4-Pad4)") (class "Default")
      (node (ref "CONN4") (pin "4") (pinfunction "4_4") (pintype "bidirectional"))
      (node (ref "R10") (pin "1") (pinfunction "1_1") (pintype "passive"))
    )
    (net (code "99") (name "Net-(CONN4-Pad5)") (class "Default")
      (node (ref "CONN4") (pin "5") (pinfunction "5_5") (pintype "bidirectional"))
      (node (ref "R12") (pin "1") (pinfunction "1_1") (pintype "passive"))
    )
    (net (code "100") (name "Net-(D1-Pad1)") (class "Default")
      (node (ref "D1") (pin "1") (pinfunction "1_1") (pintype "passive"))
      (node (ref "IH1") (pin "2") (pinfunction "2_2") (pintype "passive"))
    )
    (net (code "101") (name "Net-(D1-Pad2)") (class "Default")
      (node (ref "D1") (pin "2") (pinfunction "2_2") (pintype "passive"))
      (node (ref "IH1") (pin "8") (pinfunction "8_8") (pintype "passive"))
    )
    (net (code "102") (name "Net-(D2-Pad1)") (class "Default")
      (node (ref "D2") (pin "1") (pinfunction "1_1") (pintype "passive"))
      (node (ref "IH2") (pin "2") (pinfunction "2_2") (pintype "passive"))
    )
    (net (code "103") (name "Net-(D2-Pad2)") (class "Default")
      (node (ref "D2") (pin "2") (pinfunction "2_2") (pintype "passive"))
      (node (ref "IH2") (pin "8") (pinfunction "8_8") (pintype "passive"))
    )
    (net (code "104") (name "Net-(D3-Pad1)") (class "Default")
      (node (ref "D3") (pin "1") (pinfunction "1_1") (pintype "passive"))
      (node (ref "IH3") (pin "2") (pinfunction "2_2") (pintype "passive"))
    )
    (net (code "105") (name "Net-(D3-Pad2)") (class "Default")
      (node (ref "D3") (pin "2") (pinfunction "2_2") (pintype "passive"))
      (node (ref "IH3") (pin "8") (pinfunction "8_8") (pintype "passive"))
    )
    (net (code "106") (name "Net-(D4-Pad1)") (class "Default")
      (node (ref "D4") (pin "1") (pinfunction "1_1") (pintype "passive"))
      (node (ref "IH4") (pin "2") (pinfunction "2_2") (pintype "passive"))
    )
    (net (code "107") (name "Net-(D4-Pad2)") (class "Default")
      (node (ref "D4") (pin "2") (pinfunction "2_2") (pintype "passive"))
      (node (ref "IH4") (pin "8") (pinfunction "8_8") (pintype "passive"))
    )
    (net (code "108") (name "Net-(D5-Pad1)") (class "Default")
      (node (ref "D5") (pin "1") (pinfunction "1_1") (pintype "passive"))
      (node (ref "IH1") (pin "4") (pinfunction "4_4") (pintype "passive"))
    )
    (net (code "109") (name "Net-(D5-Pad2)") (class "Default")
      (node (ref "D5") (pin "2") (pinfunction "2_2") (pintype "passive"))
      (node (ref "IH1") (pin "6") (pinfunction "6_6") (pintype "passive"))
    )
    (net (code "110") (name "Net-(D6-Pad1)") (class "Default")
      (node (ref "D6") (pin "1") (pinfunction "1_1") (pintype "passive"))
      (node (ref "IH2") (pin "4") (pinfunction "4_4") (pintype "passive"))
    )
    (net (code "111") (name "Net-(D6-Pad2)") (class "Default")
      (node (ref "D6") (pin "2") (pinfunction "2_2") (pintype "passive"))
      (node (ref "IH2") (pin "6") (pinfunction "6_6") (pintype "passive"))
    )
    (net (code "112") (name "Net-(D7-Pad1)") (class "Default")
      (node (ref "D7") (pin "1") (pinfunction "1_1") (pintype "passive"))
      (node (ref "IH3") (pin "4") (pinfunction "4_4") (pintype "passive"))
    )
    (net (code "113") (name "Net-(D7-Pad2)") (class "Default")
      (node (ref "D7") (pin "2") (pinfunction "2_2") (pintype "passive"))
      (node (ref "IH3") (pin "6") (pinfunction "6_6") (pintype "passive"))
    )
    (net (code "114") (name "Net-(D8-Pad1)") (class "Default")
      (node (ref "D8") (pin "1") (pinfunction "1_1") (pintype "passive"))
      (node (ref "IH4") (pin "4") (pinfunction "4_4") (pintype "passive"))
    )
    (net (code "115") (name "Net-(D8-Pad2)") (class "Default")
      (node (ref "D8") (pin "2") (pinfunction "2_2") (pintype "passive"))
      (node (ref "IH4") (pin "6") (pinfunction "6_6") (pintype "passive"))
    )
    (net (code "116") (name "Net-(D9-Pad1)") (class "Default")
      (node (ref "D9") (pin "1") (pinfunction "1_1") (pintype "passive"))
      (node (ref "IH1") (pin "10") (pinfunction "10_10") (pintype "passive"))
    )
    (net (code "117") (name "Net-(D9-Pad2)") (class "Default")
      (node (ref "D9") (pin "2") (pinfunction "2_2") (pintype "passive"))
      (node (ref "IH1") (pin "16") (pinfunction "16_16") (pintype "passive"))
    )
    (net (code "118") (name "Net-(D10-Pad1)") (class "Default")
      (node (ref "D10") (pin "1") (pinfunction "1_1") (pintype "passive"))
      (node (ref "IH2") (pin "10") (pinfunction "10_10") (pintype "passive"))
    )
    (net (code "119") (name "Net-(D10-Pad2)") (class "Default")
      (node (ref "D10") (pin "2") (pinfunction "2_2") (pintype "passive"))
      (node (ref "IH2") (pin "16") (pinfunction "16_16") (pintype "passive"))
    )
    (net (code "120") (name "Net-(D11-Pad1)") (class "Default")
      (node (ref "D11") (pin "1") (pinfunction "1_1") (pintype "passive"))
      (node (ref "IH3") (pin "10") (pinfunction "10_10") (pintype "passive"))
    )
    (net (code "121") (name "Net-(D11-Pad2)") (class "Default")
      (node (ref "D11") (pin "2") (pinfunction "2_2") (pintype "passive"))
      (node (ref "IH3") (pin "16") (pinfunction "16_16") (pintype "passive"))
    )
    (net (code "122") (name "Net-(D12-Pad1)") (class "Default")
      (node (ref "D12") (pin "1") (pinfunction "1_1") (pintype "passive"))
      (node (ref "IH4") (pin "10") (pinfunction "10_10") (pintype "passive"))
    )
    (net (code "123") (name "Net-(D12-Pad2)") (class "Default")
      (node (ref "D12") (pin "2") (pinfunction "2_2") (pintype "passive"))
      (node (ref "IH4") (pin "16") (pinfunction "16_16") (pintype "passive"))
    )
    (net (code "124") (name "Net-(D13-Pad1)") (class "Default")
      (node (ref "D13") (pin "1") (pinfunction "1_1") (pintype "passive"))
      (node (ref "IH1") (pin "12") (pinfunction "12_12") (pintype "passive"))
    )
    (net (code "125") (name "Net-(D13-Pad2)") (class "Default")
      (node (ref "D13") (pin "2") (pinfunction "2_2") (pintype "passive"))
      (node (ref "IH1") (pin "14") (pinfunction "14_14") (pintype "passive"))
    )
    (net (code "126") (name "Net-(D14-Pad1)") (class "Default")
      (node (ref "D14") (pin "1") (pinfunction "1_1") (pintype "passive"))
      (node (ref "IH2") (pin "12") (pinfunction "12_12") (pintype "passive"))
    )
    (net (code "127") (name "Net-(D14-Pad2)") (class "Default")
      (node (ref "D14") (pin "2") (pinfunction "2_2") (pintype "passive"))
      (node (ref "IH2") (pin "14") (pinfunction "14_14") (pintype "passive"))
    )
    (net (code "128") (name "Net-(D15-Pad1)") (class "Default")
      (node (ref "D15") (pin "1") (pinfunction "1_1") (pintype "passive"))
      (node (ref "IH3") (pin "12") (pinfunction "12_12") (pintype "passive"))
    )
    (net (code "129") (name "Net-(D15-Pad2)") (class "Default")
      (node (ref "D15") (pin "2") (pinfunction "2_2") (pintype "passive"))
      (node (ref "IH3") (pin "14") (pinfunction "14_14") (pintype "passive"))
    )
    (net (code "130") (name "Net-(D16-Pad1)") (class "Default")
      (node (ref "D16") (pin "1") (pinfunction "1_1") (pintype "passive"))
      (node (ref "IH4") (pin "12") (pinfunction "12_12") (pintype "passive"))
    )
    (net (code "131") (name "Net-(D16-Pad2)") (class "Default")
      (node (ref "D16") (pin "2") (pinfunction "2_2") (pintype "passive"))
      (node (ref "IH4") (pin "14") (pinfunction "14_14") (pintype "passive"))
    )
    (net (code "132") (name "Net-(D18-Pad1)") (class "Default")
      (node (ref "D18") (pin "1") (pinfunction "1_1") (pintype "passive"))
      (node (ref "IH5") (pin "2") (pinfunction "2_2") (pintype "passive"))
    )
    (net (code "133") (name "Net-(D18-Pad2)") (class "Default")
      (node (ref "D18") (pin "2") (pinfunction "2_2") (pintype "passive"))
      (node (ref "IH5") (pin "8") (pinfunction "8_8") (pintype "passive"))
    )
    (net (code "134") (name "Net-(D19-Pad1)") (class "Default")
      (node (ref "D19") (pin "1") (pinfunction "1_1") (pintype "passive"))
      (node (ref "IH6") (pin "2") (pinfunction "2_2") (pintype "passive"))
    )
    (net (code "135") (name "Net-(D19-Pad2)") (class "Default")
      (node (ref "D19") (pin "2") (pinfunction "2_2") (pintype "passive"))
      (node (ref "IH6") (pin "8") (pinfunction "8_8") (pintype "passive"))
    )
    (net (code "136") (name "Net-(D20-Pad1)") (class "Default")
      (node (ref "D20") (pin "1") (pinfunction "1_1") (pintype "passive"))
      (node (ref "IH7") (pin "2") (pinfunction "2_2") (pintype "passive"))
    )
    (net (code "137") (name "Net-(D20-Pad2)") (class "Default")
      (node (ref "D20") (pin "2") (pinfunction "2_2") (pintype "passive"))
      (node (ref "IH7") (pin "8") (pinfunction "8_8") (pintype "passive"))
    )
    (net (code "138") (name "Net-(D21-Pad1)") (class "Default")
      (node (ref "D21") (pin "1") (pinfunction "1_1") (pintype "passive"))
      (node (ref "IH8") (pin "2") (pinfunction "2_2") (pintype "passive"))
    )
    (net (code "139") (name "Net-(D21-Pad2)") (class "Default")
      (node (ref "D21") (pin "2") (pinfunction "2_2") (pintype "passive"))
      (node (ref "IH8") (pin "8") (pinfunction "8_8") (pintype "passive"))
    )
    (net (code "140") (name "Net-(D22-Pad1)") (class "Default")
      (node (ref "D22") (pin "1") (pinfunction "1_1") (pintype "passive"))
      (node (ref "IH5") (pin "4") (pinfunction "4_4") (pintype "passive"))
    )
    (net (code "141") (name "Net-(D22-Pad2)") (class "Default")
      (node (ref "D22") (pin "2") (pinfunction "2_2") (pintype "passive"))
      (node (ref "IH5") (pin "6") (pinfunction "6_6") (pintype "passive"))
    )
    (net (code "142") (name "Net-(D23-Pad1)") (class "Default")
      (node (ref "D23") (pin "1") (pinfunction "1_1") (pintype "passive"))
      (node (ref "IH6") (pin "4") (pinfunction "4_4") (pintype "passive"))
    )
    (net (code "143") (name "Net-(D23-Pad2)") (class "Default")
      (node (ref "D23") (pin "2") (pinfunction "2_2") (pintype "passive"))
      (node (ref "IH6") (pin "6") (pinfunction "6_6") (pintype "passive"))
    )
    (net (code "144") (name "Net-(D24-Pad1)") (class "Default")
      (node (ref "D24") (pin "1") (pinfunction "1_1") (pintype "passive"))
      (node (ref "IH7") (pin "4") (pinfunction "4_4") (pintype "passive"))
    )
    (net (code "145") (name "Net-(D24-Pad2)") (class "Default")
      (node (ref "D24") (pin "2") (pinfunction "2_2") (pintype "passive"))
      (node (ref "IH7") (pin "6") (pinfunction "6_6") (pintype "passive"))
    )
    (net (code "146") (name "Net-(D25-Pad1)") (class "Default")
      (node (ref "D25") (pin "1") (pinfunction "1_1") (pintype "passive"))
      (node (ref "IH8") (pin "4") (pinfunction "4_4") (pintype "passive"))
    )
    (net (code "147") (name "Net-(D25-Pad2)") (class "Default")
      (node (ref "D25") (pin "2") (pinfunction "2_2") (pintype "passive"))
      (node (ref "IH8") (pin "6") (pinfunction "6_6") (pintype "passive"))
    )
    (net (code "148") (name "Net-(D26-Pad1)") (class "Default")
      (node (ref "D26") (pin "1") (pinfunction "1_1") (pintype "passive"))
      (node (ref "IH5") (pin "10") (pinfunction "10_10") (pintype "passive"))
    )
    (net (code "149") (name "Net-(D26-Pad2)") (class "Default")
      (node (ref "D26") (pin "2") (pinfunction "2_2") (pintype "passive"))
      (node (ref "IH5") (pin "16") (pinfunction "16_16") (pintype "passive"))
    )
    (net (code "150") (name "Net-(D27-Pad1)") (class "Default")
      (node (ref "D27") (pin "1") (pinfunction "1_1") (pintype "passive"))
      (node (ref "IH6") (pin "10") (pinfunction "10_10") (pintype "passive"))
    )
    (net (code "151") (name "Net-(D27-Pad2)") (class "Default")
      (node (ref "D27") (pin "2") (pinfunction "2_2") (pintype "passive"))
      (node (ref "IH6") (pin "16") (pinfunction "16_16") (pintype "passive"))
    )
    (net (code "152") (name "Net-(D28-Pad1)") (class "Default")
      (node (ref "D28") (pin "1") (pinfunction "1_1") (pintype "passive"))
      (node (ref "IH7") (pin "10") (pinfunction "10_10") (pintype "passive"))
    )
    (net (code "153") (name "Net-(D28-Pad2)") (class "Default")
      (node (ref "D28") (pin "2") (pinfunction "2_2") (pintype "passive"))
      (node (ref "IH7") (pin "16") (pinfunction "16_16") (pintype "passive"))
    )
    (net (code "154") (name "Net-(D29-Pad1)") (class "Default")
      (node (ref "D29") (pin "1") (pinfunction "1_1") (pintype "passive"))
      (node (ref "IH8") (pin "10") (pinfunction "10_10") (pintype "passive"))
    )
    (net (code "155") (name "Net-(D29-Pad2)") (class "Default")
      (node (ref "D29") (pin "2") (pinfunction "2_2") (pintype "passive"))
      (node (ref "IH8") (pin "16") (pinfunction "16_16") (pintype "passive"))
    )
    (net (code "156") (name "Net-(D30-Pad1)") (class "Default")
      (node (ref "D30") (pin "1") (pinfunction "1_1") (pintype "passive"))
      (node (ref "IH5") (pin "12") (pinfunction "12_12") (pintype "passive"))
    )
    (net (code "157") (name "Net-(D30-Pad2)") (class "Default")
      (node (ref "D30") (pin "2") (pinfunction "2_2") (pintype "passive"))
      (node (ref "IH5") (pin "14") (pinfunction "14_14") (pintype "passive"))
    )
    (net (code "158") (name "Net-(D31-Pad1)") (class "Default")
      (node (ref "D31") (pin "1") (pinfunction "1_1") (pintype "passive"))
      (node (ref "IH6") (pin "12") (pinfunction "12_12") (pintype "passive"))
    )
    (net (code "159") (name "Net-(D31-Pad2)") (class "Default")
      (node (ref "D31") (pin "2") (pinfunction "2_2") (pintype "passive"))
      (node (ref "IH6") (pin "14") (pinfunction "14_14") (pintype "passive"))
    )
    (net (code "160") (name "Net-(D32-Pad1)") (class "Default")
      (node (ref "D32") (pin "1") (pinfunction "1_1") (pintype "passive"))
      (node (ref "IH7") (pin "12") (pinfunction "12_12") (pintype "passive"))
    )
    (net (code "161") (name "Net-(D32-Pad2)") (class "Default")
      (node (ref "D32") (pin "2") (pinfunction "2_2") (pintype "passive"))
      (node (ref "IH7") (pin "14") (pinfunction "14_14") (pintype "passive"))
    )
    (net (code "162") (name "Net-(D33-Pad1)") (class "Default")
      (node (ref "D33") (pin "1") (pinfunction "1_1") (pintype "passive"))
      (node (ref "IH8") (pin "12") (pinfunction "12_12") (pintype "passive"))
    )
    (net (code "163") (name "Net-(D33-Pad2)") (class "Default")
      (node (ref "D33") (pin "2") (pinfunction "2_2") (pintype "passive"))
      (node (ref "IH8") (pin "14") (pinfunction "14_14") (pintype "passive"))
    )
    (net (code "164") (name "Net-(D35-PadA)") (class "Default")
      (node (ref "D35") (pin "A") (pinfunction "A_A") (pintype "passive"))
      (node (ref "R6") (pin "1") (pinfunction "1_1") (pintype "passive"))
    )
    (net (code "165") (name "Net-(D36-PadA)") (class "Default")
      (node (ref "D36") (pin "A") (pinfunction "A_A") (pintype "passive"))
      (node (ref "R7") (pin "1") (pinfunction "1_1") (pintype "passive"))
    )
    (net (code "166") (name "Net-(D37-PadA)") (class "Default")
      (node (ref "D37") (pin "A") (pinfunction "A_A") (pintype "passive"))
      (node (ref "R8") (pin "2") (pinfunction "2_2") (pintype "passive"))
    )
    (net (code "167") (name "Net-(Q1-D1)") (class "Default")
      (node (ref "Q1") (pin "6") (pinfunction "D1_6") (pintype "bidirectional"))
      (node (ref "R20") (pin "2") (pinfunction "2_2") (pintype "passive"))
    )
    (net (code "168") (name "Net-(Q1-D2)") (class "Default")
      (node (ref "Q1") (pin "4") (pinfunction "D2_4") (pintype "bidirectional"))
      (node (ref "R22") (pin "1") (pinfunction "1_1") (pintype "passive"))
    )
    (net (code "169") (name "Net-(Q2-D1)") (class "Default")
      (node (ref "Q2") (pin "6") (pinfunction "D1_6") (pintype "bidirectional"))
      (node (ref "R24") (pin "2") (pinfunction "2_2") (pintype "passive"))
    )
    (net (code "170") (name "Net-(Q2-D2)") (class "Default")
      (node (ref "Q2") (pin "4") (pinfunction "D2_4") (pintype "bidirectional"))
      (node (ref "R26") (pin "2") (pinfunction "2_2") (pintype "passive"))
    )
    (net (code "171") (name "Net-(Q3-D1)") (class "Default")
      (node (ref "Q3") (pin "6") (pinfunction "D1_6") (pintype "bidirectional"))
      (node (ref "R28") (pin "2") (pinfunction "2_2") (pintype "passive"))
    )
    (net (code "172") (name "Net-(Q3-D2)") (class "Default")
      (node (ref "Q3") (pin "4") (pinfunction "D2_4") (pintype "bidirectional"))
      (node (ref "R30") (pin "2") (pinfunction "2_2") (pintype "passive"))
    )
    (net (code "173") (name "Net-(U1-UCAP)") (class "Default")
      (node (ref "C8") (pin "1") (pinfunction "1_1") (pintype "passive"))
      (node (ref "U1") (pin "6") (pinfunction "UCAP_6") (pintype "bidirectional"))
    )
    (net (code "174") (name "Net-(U2-A)") (class "Default")
      (node (ref "D34") (pin "2") (pinfunction "2_2") (pintype "passive"))
      (node (ref "R5") (pin "2") (pinfunction "2_2") (pintype "passive"))
      (node (ref "U2") (pin "2") (pinfunction "A_2") (pintype "passive"))
    )
    (net (code "175") (name "Net-(U2-C)") (class "Default")
      (node (ref "CONN3") (pin "5") (pinfunction "5_5") (pintype "bidirectional"))
      (node (ref "D34") (pin "3") (pinfunction "3_3") (pintype "passive"))
      (node (ref "U2") (pin "3") (pinfunction "C_3") (pintype "passive"))
    )
    (net (code "176") (name "Net-(U7-Y0)") (class "Default")
      (node (ref "U7") (pin "15") (pinfunction "Y0_15") (pintype "output"))
      (node (ref "U8") (pin "1") (pinfunction "1B_1") (pintype "input"))
    )
    (net (code "177") (name "Net-(U7-Y1)") (class "Default")
      (node (ref "U7") (pin "14") (pinfunction "Y1_14") (pintype "output"))
      (node (ref "U8") (pin "2") (pinfunction "2B_2") (pintype "input"))
    )
    (net (code "178") (name "Net-(U7-Y2)") (class "Default")
      (node (ref "U7") (pin "13") (pinfunction "Y2_13") (pintype "output"))
      (node (ref "U8") (pin "3") (pinfunction "3B_3") (pintype "input"))
    )
    (net (code "179") (name "Net-(U7-Y3)") (class "Default")
      (node (ref "U7") (pin "12") (pinfunction "Y3_12") (pintype "output"))
      (node (ref "U8") (pin "4") (pinfunction "4B_4") (pintype "input"))
    )
    (net (code "180") (name "Net-(U7-Y4)") (class "Default")
      (node (ref "U7") (pin "11") (pinfunction "Y4_11") (pintype "output"))
      (node (ref "U8") (pin "5") (pinfunction "5B_5") (pintype "input"))
    )
    (net (code "181") (name "Net-(U7-Y5)") (class "Default")
      (node (ref "U7") (pin "10") (pinfunction "Y5_10") (pintype "output"))
      (node (ref "U8") (pin "6") (pinfunction "6B_6") (pintype "input"))
    )
    (net (code "182") (name "Net-(U7-Y6)") (class "Default")
      (node (ref "U7") (pin "9") (pinfunction "Y6_9") (pintype "output"))
      (node (ref "U8") (pin "7") (pinfunction "7B_7") (pintype "input"))
    )
    (net (code "183") (name "Net-(U7-Y7)") (class "Default")
      (node (ref "U7") (pin "7") (pinfunction "Y7_7") (pintype "output"))
      (node (ref "U8") (pin "8") (pinfunction "8B_8") (pintype "input"))
    )
    (net (code "184") (name "RESET") (class "Default")
      (node (ref "CONN2") (pin "5") (pinfunction "5_5") (pintype "passive"))
      (node (ref "R3") (pin "2") (pinfunction "2_2") (pintype "passive"))
      (node (ref "U1") (pin "13") (pinfunction "~{RESET}_13") (pintype "bidirectional"))
    )
    (net (code "185") (name "SR_CLOCK") (class "Default")
      (node (ref "U1") (pin "18") (pinfunction "PD0(OC0B/SCL/INT0)_18") (pintype "bidirectional"))
      (node (ref "U3") (pin "2") (pinfunction "CP_2") (pintype "bidirectional"))
    )
    (net (code "186") (name "SR_OUT") (class "Default")
      (node (ref "U1") (pin "22") (pinfunction "PD5(XCK1/~{CTS})_22") (pintype "bidirectional"))
      (node (ref "U3") (pin "9") (pinfunction "Q7_9") (pintype "output"))
    )
    (net (code "187") (name "SR_PARALLEL_LOAD") (class "Default")
      (node (ref "U1") (pin "19") (pinfunction "PD1(SDA/INT1)_19") (pintype "bidirectional"))
      (node (ref "U3") (pin "1") (pinfunction "~{PL}_1") (pintype "input"))
    )
    (net (code "188") (name "USB_SHIELD") (class "Default")
      (node (ref "CONN1") (pin "S1") (pinfunction "S_S1") (pintype "passive"))
      (node (ref "CONN1") (pin "S2") (pinfunction "S_S2") (pintype "passive"))
      (node (ref "L1") (pin "2") (pinfunction "2_2") (pintype "passive"))
    )
    (net (code "189") (name "XTAL1") (class "Default")
      (node (ref "C1") (pin "1") (pinfunction "1_1") (pintype "passive"))
      (node (ref "U1") (pin "17") (pinfunction "XTAL1_17") (pintype "bidirectional"))
      (node (ref "Y1") (pin "3") (pinfunction "2_3") (pintype "passive"))
    )
    (net (code "190") (name "XTAL2") (class "Default")
      (node (ref "C2") (pin "1") (pinfunction "1_1") (pintype "passive"))
      (node (ref "U1") (pin "16") (pinfunction "XTAL2_16") (pintype "bidirectional"))
      (node (ref "Y1") (pin "1") (pinfunction "1_1") (pintype "passive"))
    )
    (net (code "191") (name "unconnected-(CONN3-Pad1)") (class "Default")
      (node (ref "CONN3") (pin "1") (pinfunction "1_1") (pintype "bidirectional"))
    )
    (net (code "192") (name "unconnected-(CONN3-Pad2)") (class "Default")
      (node (ref "CONN3") (pin "2") (pinfunction "2_2") (pintype "passive"))
    )
    (net (code "193") (name "unconnected-(CONN3-Pad3)") (class "Default")
      (node (ref "CONN3") (pin "3") (pinfunction "3_3") (pintype "bidirectional"))
    )
    (net (code "194") (name "unconnected-(CONN4-Pad1)") (class "Default")
      (node (ref "CONN4") (pin "1") (pinfunction "1_1") (pintype "bidirectional"))
    )
    (net (code "195") (name "unconnected-(CONN4-Pad3)") (class "Default")
      (node (ref "CONN4") (pin "3") (pinfunction "3_3") (pintype "bidirectional"))
    )
    (net (code "196") (name "unconnected-(D34-Pad1)") (class "Default")
      (node (ref "D34") (pin "1") (pinfunction "1_1") (pintype "passive"))
    )
    (net (code "197") (name "unconnected-(U1-PB0(SS{slash}PCINT0)-Pad8)") (class "Default")
      (node (ref "U1") (pin "8") (pinfunction "PB0(SS/PCINT0)_8") (pintype "bidirectional"))
    )
    (net (code "198") (name "unconnected-(U3-DS-Pad10)") (class "Default")
      (node (ref "U3") (pin "10") (pinfunction "DS_10") (pintype "bidirectional"))
    )
    (net (code "199") (name "unconnected-(U3-~{Q7}-Pad7)") (class "Default")
      (node (ref "U3") (pin "7") (pinfunction "~{Q7}_7") (pintype "output"))
    )
    (net (code "200") (name "unconnected-(VR1-NC-Pad4)") (class "Default")
      (node (ref "VR1") (pin "4") (pinfunction "NC_4") (pintype "no_connect"))
    )
  )
)
